# Quectel-2560-v2_3.net
KiCad netlist of a schematic drawn in EAGLE
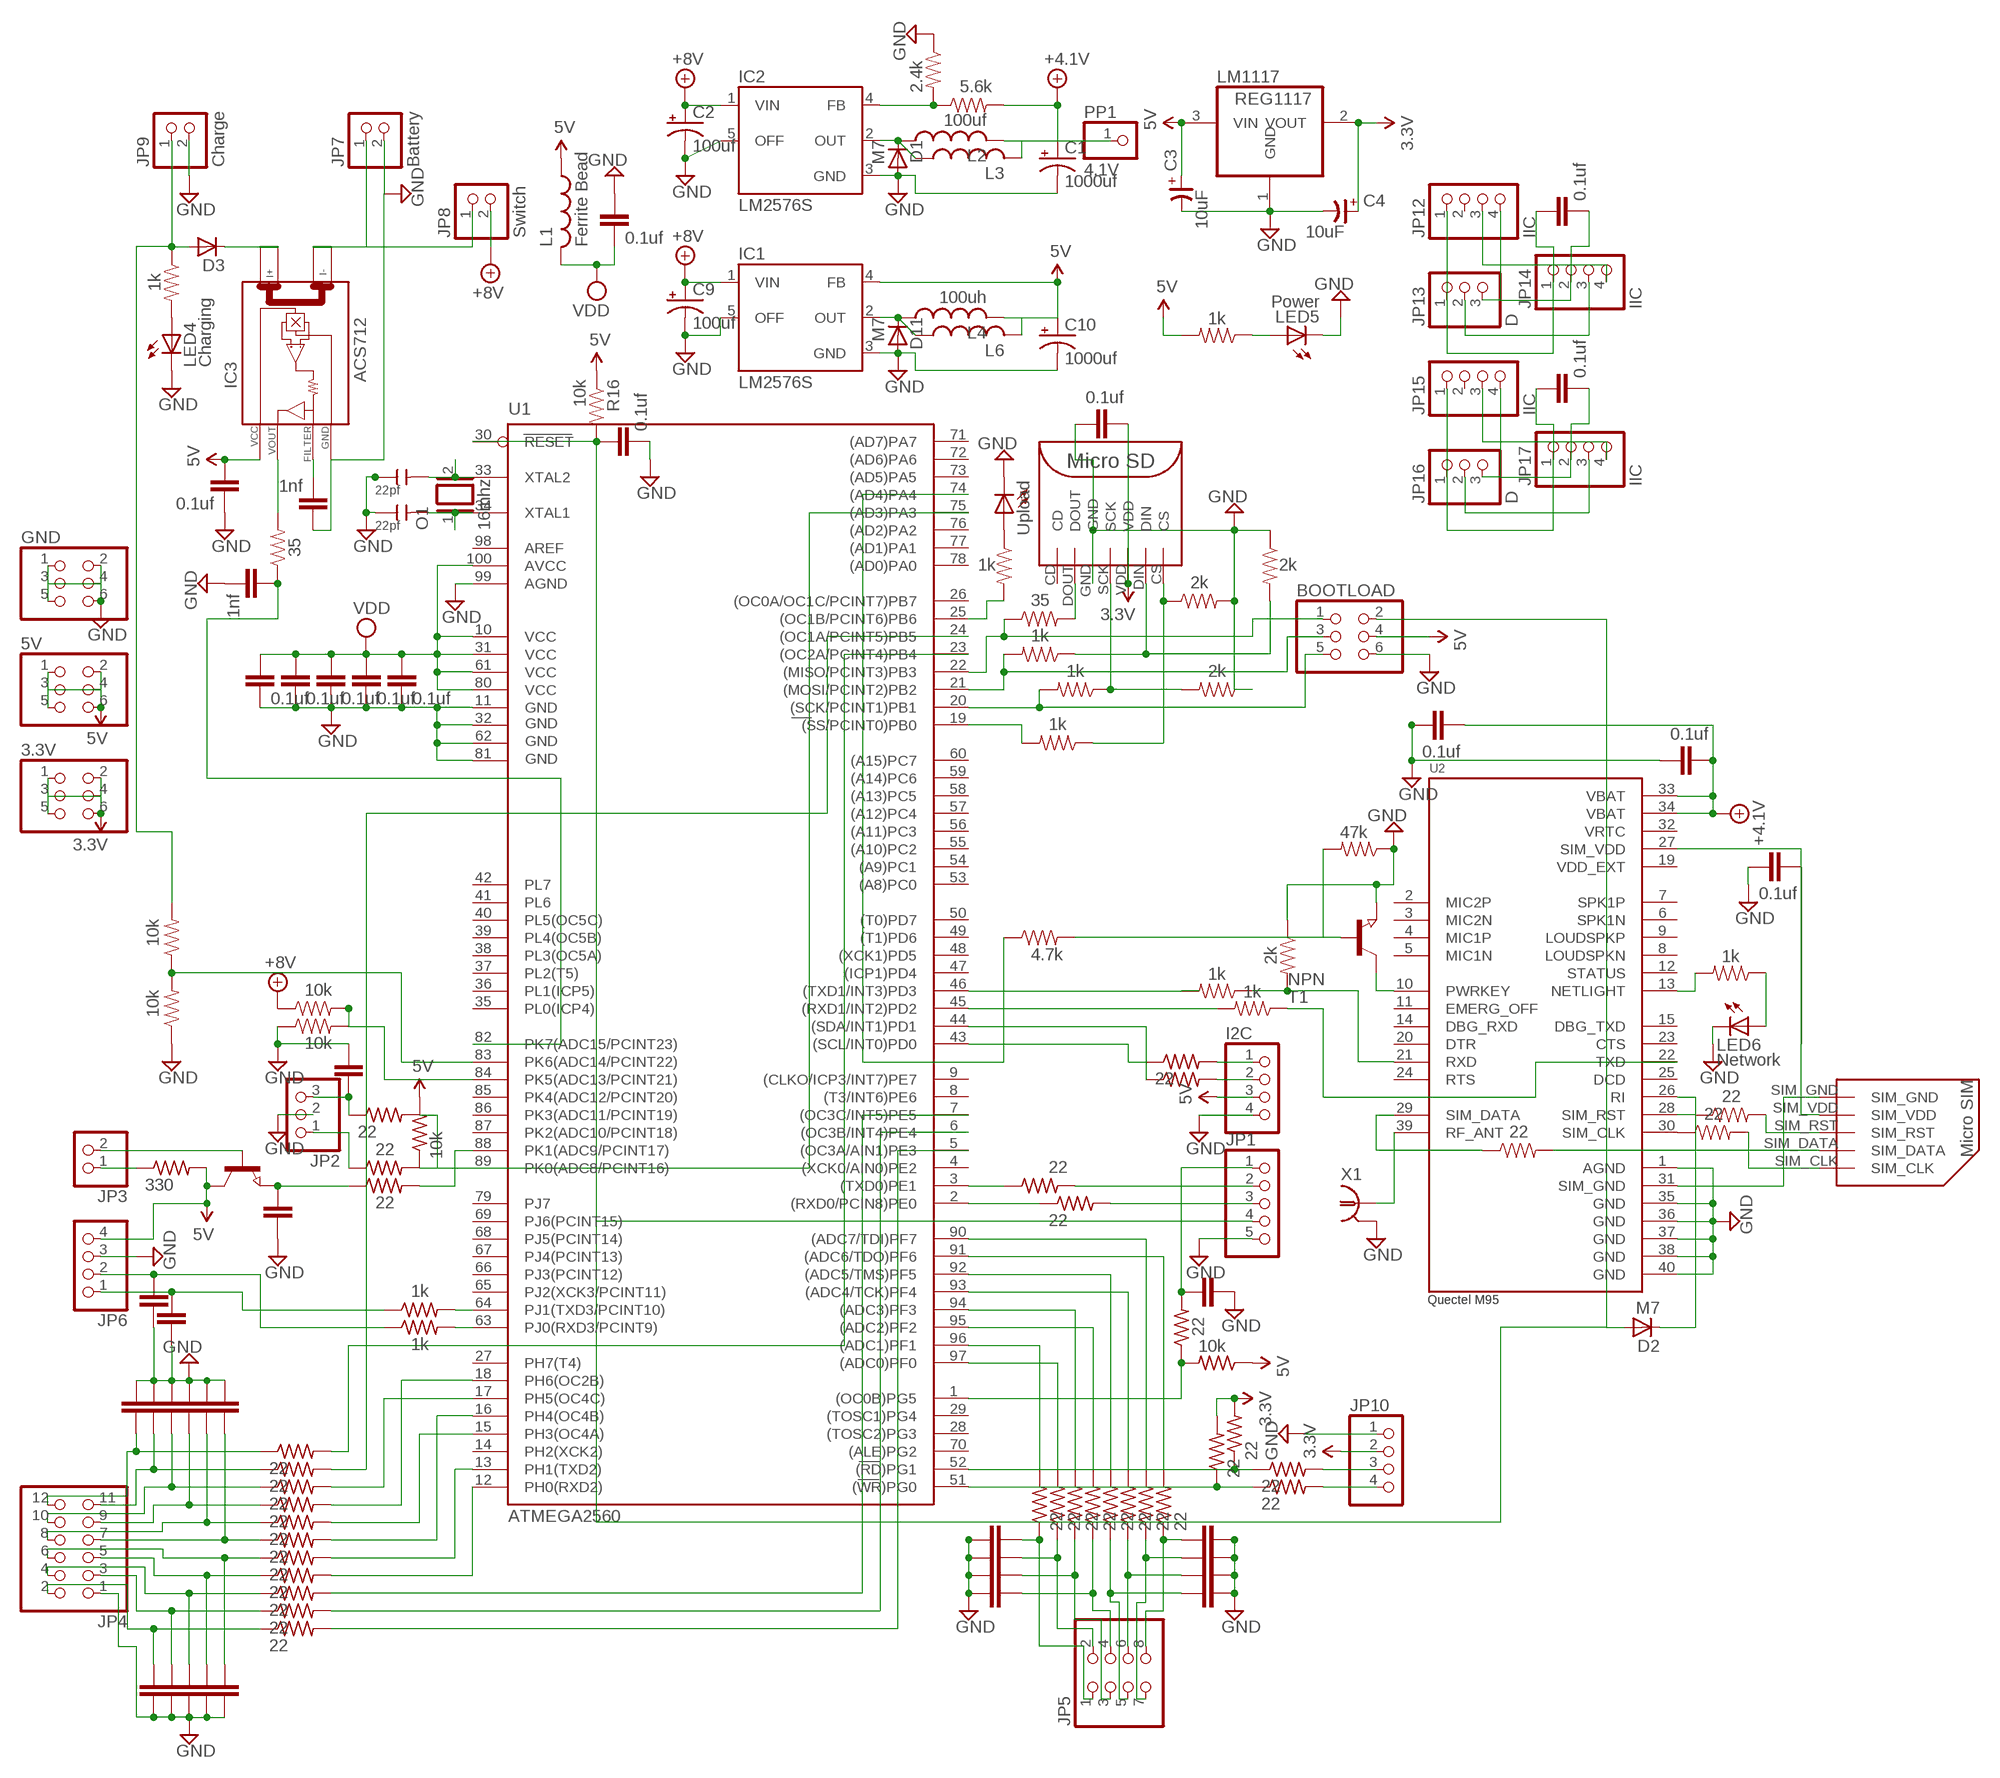
[diagram p0: schematic, sheet 1]

(export (version "E")
  (design (tool "Eeschema 10.0.6"))
  (components
    (comp (ref "3.3V")
      (value "PINHD-2X3")
      (footprint "eagle-import:2X03")
      (libsource (lib "eagle-import") (part "PINHD-2X3"))
    )
    (comp (ref "5V")
      (value "PINHD-2X3")
      (footprint "eagle-import:2X03")
      (libsource (lib "eagle-import") (part "PINHD-2X3"))
    )
    (comp (ref "BOOTLOAD")
      (value "PINHD-2X3")
      (footprint "eagle-import:2X03")
      (libsource (lib "eagle-import") (part "PINHD-2X3"))
    )
    (comp (ref "C1")
      (value "1000uf")
      (footprint "eagle-import:153CLV-1012")
      (libsource (lib "eagle-import") (part "CPOL-US153CLV-1012"))
    )
    (comp (ref "C2")
      (value "100uf")
      (footprint "eagle-import:CT7343")
      (libsource (lib "eagle-import") (part "CPOL-USCT7343"))
    )
    (comp (ref "C3")
      (value "10uF")
      (footprint "eagle-import:3528_T")
      (libsource (lib "eagle-import") (part "CP-3528"))
    )
    (comp (ref "C4")
      (value "10uF")
      (footprint "eagle-import:3528_T")
      (libsource (lib "eagle-import") (part "CP-3528"))
    )
    (comp (ref "C7")
      (value "22pf")
      (footprint "eagle-import:C0805")
      (fields (field (name "MPN") "CC0805JRNPO9BN220"))
      (libsource (lib "eagle-import") (part "CERAMIC-22PF-50V-5%-NPO(0805)"))
    )
    (comp (ref "C8")
      (value "22pf")
      (footprint "eagle-import:C0805")
      (fields (field (name "MPN") "CC0805JRNPO9BN220"))
      (libsource (lib "eagle-import") (part "CERAMIC-22PF-50V-5%-NPO(0805)"))
    )
    (comp (ref "C9")
      (value "100uf")
      (footprint "eagle-import:CT7343")
      (libsource (lib "eagle-import") (part "CPOL-USCT7343"))
    )
    (comp (ref "C10")
      (value "1000uf")
      (footprint "eagle-import:153CLV-1012")
      (libsource (lib "eagle-import") (part "CPOL-US153CLV-1012"))
    )
    (comp (ref "D1")
      (value "M7")
      (footprint "eagle-import:SOD106A")
      (fields (field (name "MPN") "BYS10/45"))
      (libsource (lib "eagle-import") (part "BYS10"))
    )
    (comp (ref "D2")
      (value "M7")
      (footprint "eagle-import:SOD106A")
      (fields (field (name "MPN") "BYS10/45"))
      (libsource (lib "eagle-import") (part "BYS10"))
    )
    (comp (ref "D3")
      (value "BYS10")
      (footprint "eagle-import:SOD106A")
      (fields (field (name "MPN") "BYS10/45"))
      (libsource (lib "eagle-import") (part "BYS10"))
    )
    (comp (ref "D11")
      (value "M7")
      (footprint "eagle-import:SOD106A")
      (fields (field (name "MPN") "BYS10/45"))
      (libsource (lib "eagle-import") (part "BYS10"))
    )
    (comp (ref "DC1")
      (value "0.1uf")
      (footprint "eagle-import:C0805")
      (libsource (lib "eagle-import") (part "C-EUC0805"))
    )
    (comp (ref "DC2")
      (value "0.1uf")
      (footprint "eagle-import:C0805")
      (libsource (lib "eagle-import") (part "C-EUC0805"))
    )
    (comp (ref "DC3")
      (value "0.1uf")
      (footprint "eagle-import:C0805")
      (libsource (lib "eagle-import") (part "C-EUC0805"))
    )
    (comp (ref "DC4")
      (value "0.1uf")
      (footprint "eagle-import:C0805")
      (libsource (lib "eagle-import") (part "C-EUC0805"))
    )
    (comp (ref "DC5")
      (value "0.1uf")
      (footprint "eagle-import:C0805")
      (libsource (lib "eagle-import") (part "C-EUC0805"))
    )
    (comp (ref "DC6")
      (value "0.1uf")
      (footprint "eagle-import:C0805")
      (libsource (lib "eagle-import") (part "C-EUC0805"))
    )
    (comp (ref "DC7")
      (value "0.1uf")
      (footprint "eagle-import:C0805")
      (libsource (lib "eagle-import") (part "C-EUC0805"))
    )
    (comp (ref "DC8")
      (value "0.1uf")
      (footprint "eagle-import:C0805")
      (libsource (lib "eagle-import") (part "C-EUC0805"))
    )
    (comp (ref "DC9")
      (value "0.1uf")
      (footprint "eagle-import:C0805")
      (libsource (lib "eagle-import") (part "C-EUC0805"))
    )
    (comp (ref "DC10")
      (value "0.1uf")
      (footprint "eagle-import:C0805")
      (libsource (lib "eagle-import") (part "C-EUC0805"))
    )
    (comp (ref "DC11")
      (value "0.1uf")
      (footprint "eagle-import:C0805")
      (libsource (lib "eagle-import") (part "C-EUC0805"))
    )
    (comp (ref "DC12")
      (value "1nf")
      (footprint "eagle-import:C0805")
      (libsource (lib "eagle-import") (part "C-EUC0805"))
    )
    (comp (ref "DC13")
      (value "1nf")
      (footprint "eagle-import:C0805")
      (libsource (lib "eagle-import") (part "C-EUC0805"))
    )
    (comp (ref "DC14")
      (value "1nf")
      (footprint "eagle-import:C0805")
      (libsource (lib "eagle-import") (part "C-EUC0805"))
    )
    (comp (ref "DC15")
      (value "0.1uf")
      (footprint "eagle-import:C0805")
      (libsource (lib "eagle-import") (part "C-EUC0805"))
    )
    (comp (ref "DC16")
      (value "1nf")
      (footprint "eagle-import:C0805")
      (libsource (lib "eagle-import") (part "C-EUC0805"))
    )
    (comp (ref "DC17")
      (value "1nf")
      (footprint "eagle-import:C0805")
      (libsource (lib "eagle-import") (part "C-EUC0805"))
    )
    (comp (ref "DC18")
      (value "0.1uf")
      (footprint "eagle-import:C0805")
      (libsource (lib "eagle-import") (part "C-EUC0805"))
    )
    (comp (ref "DC19")
      (value "0.1uf")
      (footprint "eagle-import:C0805")
      (libsource (lib "eagle-import") (part "C-EUC0805"))
    )
    (comp (ref "DC20")
      (value "1nf")
      (footprint "eagle-import:C0805")
      (libsource (lib "eagle-import") (part "C-EUC0805"))
    )
    (comp (ref "DC21")
      (value "1nf")
      (footprint "eagle-import:C0805")
      (libsource (lib "eagle-import") (part "C-EUC0805"))
    )
    (comp (ref "DC22")
      (value "1nf")
      (footprint "eagle-import:C0805")
      (libsource (lib "eagle-import") (part "C-EUC0805"))
    )
    (comp (ref "DC23")
      (value "1nf")
      (footprint "eagle-import:C0805")
      (libsource (lib "eagle-import") (part "C-EUC0805"))
    )
    (comp (ref "DC24")
      (value "1nf")
      (footprint "eagle-import:C0805")
      (libsource (lib "eagle-import") (part "C-EUC0805"))
    )
    (comp (ref "DC25")
      (value "1nf")
      (footprint "eagle-import:C0805")
      (libsource (lib "eagle-import") (part "C-EUC0805"))
    )
    (comp (ref "DC26")
      (value "1nf")
      (footprint "eagle-import:C0805")
      (libsource (lib "eagle-import") (part "C-EUC0805"))
    )
    (comp (ref "DC27")
      (value "1nf")
      (footprint "eagle-import:C0805")
      (libsource (lib "eagle-import") (part "C-EUC0805"))
    )
    (comp (ref "DC28")
      (value "1nf")
      (footprint "eagle-import:C0805")
      (libsource (lib "eagle-import") (part "C-EUC0805"))
    )
    (comp (ref "DC29")
      (value "1nf")
      (footprint "eagle-import:C0805")
      (libsource (lib "eagle-import") (part "C-EUC0805"))
    )
    (comp (ref "DC30")
      (value "1nf")
      (footprint "eagle-import:C0805")
      (libsource (lib "eagle-import") (part "C-EUC0805"))
    )
    (comp (ref "DC31")
      (value "1nf")
      (footprint "eagle-import:C0805")
      (libsource (lib "eagle-import") (part "C-EUC0805"))
    )
    (comp (ref "DC32")
      (value "1nf")
      (footprint "eagle-import:C0805")
      (libsource (lib "eagle-import") (part "C-EUC0805"))
    )
    (comp (ref "DC33")
      (value "1nf")
      (footprint "eagle-import:C0805")
      (libsource (lib "eagle-import") (part "C-EUC0805"))
    )
    (comp (ref "DC34")
      (value "1nf")
      (footprint "eagle-import:C0805")
      (libsource (lib "eagle-import") (part "C-EUC0805"))
    )
    (comp (ref "DC35")
      (value "1nf")
      (footprint "eagle-import:C0805")
      (libsource (lib "eagle-import") (part "C-EUC0805"))
    )
    (comp (ref "DC36")
      (value "1nf")
      (footprint "eagle-import:C0805")
      (libsource (lib "eagle-import") (part "C-EUC0805"))
    )
    (comp (ref "DC37")
      (value "1nf")
      (footprint "eagle-import:C0805")
      (libsource (lib "eagle-import") (part "C-EUC0805"))
    )
    (comp (ref "DC38")
      (value "1nf")
      (footprint "eagle-import:C0805")
      (libsource (lib "eagle-import") (part "C-EUC0805"))
    )
    (comp (ref "DC39")
      (value "1nf")
      (footprint "eagle-import:C0805")
      (libsource (lib "eagle-import") (part "C-EUC0805"))
    )
    (comp (ref "DC40")
      (value "1nf")
      (footprint "eagle-import:C0805")
      (libsource (lib "eagle-import") (part "C-EUC0805"))
    )
    (comp (ref "GND")
      (value "PINHD-2X3")
      (footprint "eagle-import:2X03")
      (libsource (lib "eagle-import") (part "PINHD-2X3"))
    )
    (comp (ref "I2C")
      (value "PINHD-1X4")
      (footprint "eagle-import:1X04")
      (libsource (lib "eagle-import") (part "pinhead_325_PINHD-1X4"))
    )
    (comp (ref "IC1")
      (value "LM2576S")
      (footprint "eagle-import:TO263-5")
      (libsource (lib "eagle-import") (part "LM2576S"))
    )
    (comp (ref "IC2")
      (value "LM2576S")
      (footprint "eagle-import:TO263-5")
      (libsource (lib "eagle-import") (part "LM2576S"))
    )
    (comp (ref "IC3")
      (value "ACS712")
      (footprint "eagle-import:SO08")
      (libsource (lib "eagle-import") (part "ACS712"))
    )
    (comp (ref "JP1")
      (value "PINHD-1X5")
      (footprint "eagle-import:1X05")
      (libsource (lib "eagle-import") (part "PINHD-1X5"))
    )
    (comp (ref "JP2")
      (value "PINHD-1X3")
      (footprint "eagle-import:1X03")
      (libsource (lib "eagle-import") (part "pinhead_325_PINHD-1X3"))
    )
    (comp (ref "JP3")
      (value "PINHD-1X2")
      (footprint "eagle-import:1X02")
      (libsource (lib "eagle-import") (part "pinhead_325_PINHD-1X2"))
    )
    (comp (ref "JP4")
      (value "PINHD-2X6")
      (footprint "eagle-import:2X06")
      (libsource (lib "eagle-import") (part "PINHD-2X6"))
    )
    (comp (ref "JP5")
      (value "PINHD-2X4")
      (footprint "eagle-import:2X04")
      (libsource (lib "eagle-import") (part "PINHD-2X4"))
    )
    (comp (ref "JP6")
      (value "PINHD-1X4")
      (footprint "eagle-import:1X04")
      (libsource (lib "eagle-import") (part "pinhead_325_PINHD-1X4"))
    )
    (comp (ref "JP7")
      (value "Battery")
      (footprint "eagle-import:1X02")
      (libsource (lib "eagle-import") (part "PINHD-1X2"))
    )
    (comp (ref "JP8")
      (value "Switch")
      (footprint "eagle-import:1X02")
      (libsource (lib "eagle-import") (part "PINHD-1X2"))
    )
    (comp (ref "JP9")
      (value "Charge")
      (footprint "eagle-import:1X02")
      (libsource (lib "eagle-import") (part "PINHD-1X2"))
    )
    (comp (ref "JP10")
      (value "PINHD-1X4")
      (footprint "eagle-import:1X04")
      (libsource (lib "eagle-import") (part "pinhead_325_PINHD-1X4"))
    )
    (comp (ref "JP12")
      (value "IIC")
      (footprint "eagle-import:1X04")
      (libsource (lib "eagle-import") (part "PINHD-1X4"))
    )
    (comp (ref "JP13")
      (value "D")
      (footprint "eagle-import:1X03")
      (libsource (lib "eagle-import") (part "PINHD-1X3"))
    )
    (comp (ref "JP14")
      (value "IIC")
      (footprint "eagle-import:1X04")
      (libsource (lib "eagle-import") (part "PINHD-1X4"))
    )
    (comp (ref "JP15")
      (value "IIC")
      (footprint "eagle-import:1X04")
      (libsource (lib "eagle-import") (part "PINHD-1X4"))
    )
    (comp (ref "JP16")
      (value "D")
      (footprint "eagle-import:1X03")
      (libsource (lib "eagle-import") (part "PINHD-1X3"))
    )
    (comp (ref "JP17")
      (value "IIC")
      (footprint "eagle-import:1X04")
      (libsource (lib "eagle-import") (part "PINHD-1X4"))
    )
    (comp (ref "L1")
      (value "Ferrite Bead")
      (footprint "eagle-import:L2012C")
      (libsource (lib "eagle-import") (part "L-USL2012C"))
    )
    (comp (ref "L2")
      (value "100uf")
      (footprint "eagle-import:PIS2816")
      (libsource (lib "eagle-import") (part "L-USPIS2816"))
    )
    (comp (ref "L3")
      (value "L-US6000-XXX-RC")
      (footprint "eagle-import:6000-XXXX-RC")
      (libsource (lib "eagle-import") (part "L-US6000-XXX-RC"))
    )
    (comp (ref "L4")
      (value "100uh")
      (footprint "eagle-import:PIS2816")
      (libsource (lib "eagle-import") (part "L-USPIS2816"))
    )
    (comp (ref "L6")
      (value "L-US6000-XXX-RC")
      (footprint "eagle-import:6000-XXXX-RC")
      (libsource (lib "eagle-import") (part "L-US6000-XXX-RC"))
    )
    (comp (ref "LED2")
      (value "Upload")
      (footprint "eagle-import:CHIP-LED0805")
      (libsource (lib "eagle-import") (part "LEDCHIP-LED0805"))
    )
    (comp (ref "LED4")
      (value "Charging")
      (footprint "eagle-import:CHIP-LED0805")
      (libsource (lib "eagle-import") (part "LEDCHIP-LED0805"))
    )
    (comp (ref "LED5")
      (value "Power")
      (footprint "eagle-import:CHIP-LED0805")
      (libsource (lib "eagle-import") (part "LEDCHIP-LED0805"))
    )
    (comp (ref "LED6")
      (value "Network")
      (footprint "eagle-import:CHIP-LED0805")
      (libsource (lib "eagle-import") (part "LEDCHIP-LED0805"))
    )
    (comp (ref "LM1117")
      (value "REG1117")
      (footprint "eagle-import:SOT223")
      (libsource (lib "eagle-import") (part "REG1117"))
    )
    (comp (ref "O1")
      (value "16mhz")
      (footprint "eagle-import:QS")
      (libsource (lib "eagle-import") (part "XTAL/S"))
    )
    (comp (ref "PP1")
      (value "4.1V")
      (footprint "eagle-import:1X01")
      (libsource (lib "eagle-import") (part "PINHD-1X1"))
    )
    (comp (ref "R1")
      (value "35")
      (footprint "eagle-import:0805")
      (libsource (lib "eagle-import") (part "RESISTOR0805-RES"))
    )
    (comp (ref "R2")
      (value "47k")
      (footprint "eagle-import:0805")
      (libsource (lib "eagle-import") (part "RESISTOR0805-RES"))
    )
    (comp (ref "R3")
      (value "4.7k")
      (footprint "eagle-import:0805")
      (libsource (lib "eagle-import") (part "RESISTOR0805-RES"))
    )
    (comp (ref "R4")
      (value "22")
      (footprint "eagle-import:R0805")
      (libsource (lib "eagle-import") (part "R-US_R0805"))
    )
    (comp (ref "R5")
      (value "22")
      (footprint "eagle-import:R0805")
      (libsource (lib "eagle-import") (part "R-US_R0805"))
    )
    (comp (ref "R6")
      (value "1k")
      (footprint "eagle-import:0805")
      (libsource (lib "eagle-import") (part "RESISTOR0805-RES"))
    )
    (comp (ref "R7")
      (value "1k")
      (footprint "eagle-import:0805")
      (libsource (lib "eagle-import") (part "RESISTOR0805-RES"))
    )
    (comp (ref "R8")
      (value "1k")
      (footprint "eagle-import:0805")
      (libsource (lib "eagle-import") (part "RESISTOR0805-RES"))
    )
    (comp (ref "R9")
      (value "2k")
      (footprint "eagle-import:0805")
      (libsource (lib "eagle-import") (part "RESISTOR0805-RES"))
    )
    (comp (ref "R10")
      (value "22")
      (footprint "eagle-import:0805")
      (libsource (lib "eagle-import") (part "RESISTOR0805-RES"))
    )
    (comp (ref "R11")
      (value "22")
      (footprint "eagle-import:0805")
      (libsource (lib "eagle-import") (part "RESISTOR0805-RES"))
    )
    (comp (ref "R12")
      (value "22")
      (footprint "eagle-import:R0805")
      (libsource (lib "eagle-import") (part "R-US_R0805"))
    )
    (comp (ref "R13")
      (value "22")
      (footprint "eagle-import:R0805")
      (libsource (lib "eagle-import") (part "R-US_R0805"))
    )
    (comp (ref "R14")
      (value "1k")
      (footprint "eagle-import:0805")
      (libsource (lib "eagle-import") (part "RESISTOR0805-RES"))
    )
    (comp (ref "R15")
      (value "1k")
      (footprint "eagle-import:0805")
      (libsource (lib "eagle-import") (part "RESISTOR0805-RES"))
    )
    (comp (ref "R16")
      (value "10k")
      (footprint "eagle-import:0805")
      (libsource (lib "eagle-import") (part "RESISTOR0805-RES"))
    )
    (comp (ref "R17")
      (value "1k")
      (footprint "eagle-import:0805")
      (libsource (lib "eagle-import") (part "RESISTOR0805-RES"))
    )
    (comp (ref "R18")
      (value "1k")
      (footprint "eagle-import:0805")
      (libsource (lib "eagle-import") (part "RESISTOR0805-RES"))
    )
    (comp (ref "R19")
      (value "22")
      (footprint "eagle-import:R0805")
      (libsource (lib "eagle-import") (part "R-US_R0805"))
    )
    (comp (ref "R20")
      (value "22")
      (footprint "eagle-import:R0805")
      (libsource (lib "eagle-import") (part "R-US_R0805"))
    )
    (comp (ref "R21")
      (value "22")
      (footprint "eagle-import:R0805")
      (libsource (lib "eagle-import") (part "R-US_R0805"))
    )
    (comp (ref "R22")
      (value "22")
      (footprint "eagle-import:R0805")
      (libsource (lib "eagle-import") (part "R-US_R0805"))
    )
    (comp (ref "R23")
      (value "2k")
      (footprint "eagle-import:0805")
      (libsource (lib "eagle-import") (part "RESISTOR0805-RES"))
    )
    (comp (ref "R24")
      (value "2k")
      (footprint "eagle-import:0805")
      (libsource (lib "eagle-import") (part "RESISTOR0805-RES"))
    )
    (comp (ref "R25")
      (value "1k")
      (footprint "eagle-import:0805")
      (libsource (lib "eagle-import") (part "RESISTOR0805-RES"))
    )
    (comp (ref "R26")
      (value "1k")
      (footprint "eagle-import:0805")
      (libsource (lib "eagle-import") (part "RESISTOR0805-RES"))
    )
    (comp (ref "R27")
      (value "22")
      (footprint "eagle-import:R0805")
      (libsource (lib "eagle-import") (part "R-US_R0805"))
    )
    (comp (ref "R28")
      (value "22")
      (footprint "eagle-import:R0805")
      (libsource (lib "eagle-import") (part "R-US_R0805"))
    )
    (comp (ref "R29")
      (value "2k")
      (footprint "eagle-import:0805")
      (libsource (lib "eagle-import") (part "RESISTOR0805-RES"))
    )
    (comp (ref "R30")
      (value "22")
      (footprint "eagle-import:R0805")
      (libsource (lib "eagle-import") (part "R-US_R0805"))
    )
    (comp (ref "R31")
      (value "22")
      (footprint "eagle-import:R0805")
      (libsource (lib "eagle-import") (part "R-US_R0805"))
    )
    (comp (ref "R32")
      (value "22")
      (footprint "eagle-import:R0805")
      (libsource (lib "eagle-import") (part "R-US_R0805"))
    )
    (comp (ref "R33")
      (value "22")
      (footprint "eagle-import:R0805")
      (libsource (lib "eagle-import") (part "R-US_R0805"))
    )
    (comp (ref "R34")
      (value "22")
      (footprint "eagle-import:R0805")
      (libsource (lib "eagle-import") (part "R-US_R0805"))
    )
    (comp (ref "R35")
      (value "35")
      (footprint "eagle-import:0805")
      (libsource (lib "eagle-import") (part "RESISTOR0805-RES"))
    )
    (comp (ref "R36")
      (value "22")
      (footprint "eagle-import:R0805")
      (libsource (lib "eagle-import") (part "R-US_R0805"))
    )
    (comp (ref "R37")
      (value "22")
      (footprint "eagle-import:R0805")
      (libsource (lib "eagle-import") (part "R-US_R0805"))
    )
    (comp (ref "R38")
      (value "22")
      (footprint "eagle-import:R0805")
      (libsource (lib "eagle-import") (part "R-US_R0805"))
    )
    (comp (ref "R39")
      (value "22")
      (footprint "eagle-import:R0805")
      (libsource (lib "eagle-import") (part "R-US_R0805"))
    )
    (comp (ref "R40")
      (value "22")
      (footprint "eagle-import:R0805")
      (libsource (lib "eagle-import") (part "R-US_R0805"))
    )
    (comp (ref "R41")
      (value "22")
      (footprint "eagle-import:R0805")
      (libsource (lib "eagle-import") (part "R-US_R0805"))
    )
    (comp (ref "R42")
      (value "22")
      (footprint "eagle-import:R0805")
      (libsource (lib "eagle-import") (part "R-US_R0805"))
    )
    (comp (ref "R43")
      (value "10k")
      (footprint "eagle-import:0805")
      (libsource (lib "eagle-import") (part "RESISTOR0805-RES"))
    )
    (comp (ref "R44")
      (value "10k")
      (footprint "eagle-import:0805")
      (libsource (lib "eagle-import") (part "RESISTOR0805-RES"))
    )
    (comp (ref "R45")
      (value "2.4k")
      (footprint "eagle-import:0805")
      (libsource (lib "eagle-import") (part "RESISTOR0805-RES"))
    )
    (comp (ref "R46")
      (value "5.6k")
      (footprint "eagle-import:0805")
      (libsource (lib "eagle-import") (part "RESISTOR0805-RES"))
    )
    (comp (ref "R47")
      (value "22")
      (footprint "eagle-import:0805")
      (libsource (lib "eagle-import") (part "RESISTOR0805-RES"))
    )
    (comp (ref "R48")
      (value "22")
      (footprint "eagle-import:R0805")
      (libsource (lib "eagle-import") (part "R-US_R0805"))
    )
    (comp (ref "R49")
      (value "22")
      (footprint "eagle-import:R0805")
      (libsource (lib "eagle-import") (part "R-US_R0805"))
    )
    (comp (ref "R50")
      (value "10k")
      (footprint "eagle-import:R0805")
      (libsource (lib "eagle-import") (part "R-US_R0805"))
    )
    (comp (ref "R51")
      (value "22")
      (footprint "eagle-import:R0805")
      (libsource (lib "eagle-import") (part "R-US_R0805"))
    )
    (comp (ref "R52")
      (value "330")
      (footprint "eagle-import:R0805")
      (libsource (lib "eagle-import") (part "R-US_R0805"))
    )
    (comp (ref "R53")
      (value "22")
      (footprint "eagle-import:R0805")
      (libsource (lib "eagle-import") (part "R-US_R0805"))
    )
    (comp (ref "R54")
      (value "22")
      (footprint "eagle-import:R0805")
      (libsource (lib "eagle-import") (part "R-US_R0805"))
    )
    (comp (ref "R55")
      (value "10k")
      (footprint "eagle-import:R0805")
      (libsource (lib "eagle-import") (part "R-US_R0805"))
    )
    (comp (ref "R56")
      (value "10k")
      (footprint "eagle-import:0805")
      (libsource (lib "eagle-import") (part "RESISTOR0805-RES"))
    )
    (comp (ref "R57")
      (value "10k")
      (footprint "eagle-import:0805")
      (libsource (lib "eagle-import") (part "RESISTOR0805-RES"))
    )
    (comp (ref "R58")
      (value "1k")
      (footprint "eagle-import:R0805")
      (libsource (lib "eagle-import") (part "R-US_R0805"))
    )
    (comp (ref "R59")
      (value "1k")
      (footprint "eagle-import:R0805")
      (libsource (lib "eagle-import") (part "R-US_R0805"))
    )
    (comp (ref "R60")
      (value "22")
      (footprint "eagle-import:R0805")
      (libsource (lib "eagle-import") (part "R-US_R0805"))
    )
    (comp (ref "R61")
      (value "22")
      (footprint "eagle-import:R0805")
      (libsource (lib "eagle-import") (part "R-US_R0805"))
    )
    (comp (ref "R62")
      (value "22")
      (footprint "eagle-import:R0805")
      (libsource (lib "eagle-import") (part "R-US_R0805"))
    )
    (comp (ref "R63")
      (value "22")
      (footprint "eagle-import:R0805")
      (libsource (lib "eagle-import") (part "R-US_R0805"))
    )
    (comp (ref "T1")
      (value "NPN")
      (footprint "eagle-import:SOT23")
      (libsource (lib "eagle-import") (part "NPN-TRANSISTOR_SOT23"))
    )
    (comp (ref "T2")
      (value "NPN")
      (footprint "eagle-import:SOT23")
      (libsource (lib "eagle-import") (part "NPN-TRANSISTOR_SOT23"))
    )
    (comp (ref "U$1")
      (value "MICROSD")
      (footprint "eagle-import:MICROSD")
      (libsource (lib "eagle-import") (part "MICROSD"))
    )
    (comp (ref "U$2")
      (value "MICROSIM")
      (footprint "eagle-import:MICROSIM")
      (libsource (lib "eagle-import") (part "MICROSIM"))
    )
    (comp (ref "U1")
      (value "ATMEGA2560")
      (footprint "eagle-import:TQFP100")
      (libsource (lib "eagle-import") (part "ATMEGA2560AU"))
    )
    (comp (ref "U2")
      (value "Quectel M95")
      (footprint "eagle-import:XCVR_M95")
      (libsource (lib "eagle-import") (part "M95"))
    )
    (comp (ref "X1")
      (value "LTI-SASF54GT")
      (footprint "eagle-import:LTI-SASF54GT")
      (libsource (lib "eagle-import") (part "LTI-SASF54GT"))
    )
  )
  (nets
    (net (code "1") (name "+4.1V") (class "Default")
      (node (ref "C1") (pin "+") (pinfunction "+_+") (pintype "passive"))
      (node (ref "DC6") (pin "2") (pinfunction "2_2") (pintype "passive"))
      (node (ref "DC7") (pin "2") (pinfunction "2_2") (pintype "passive"))
      (node (ref "L2") (pin "2") (pinfunction "2_2") (pintype "passive"))
      (node (ref "L3") (pin "2") (pinfunction "2_2") (pintype "passive"))
      (node (ref "PP1") (pin "1") (pinfunction "1_1") (pintype "passive"))
      (node (ref "R46") (pin "2") (pinfunction "2_2") (pintype "passive"))
      (node (ref "U2") (pin "33") (pinfunction "VBAT_33") (pintype "power_in"))
      (node (ref "U2") (pin "34") (pinfunction "VBAT_34") (pintype "power_in"))
    )
    (net (code "2") (name "+8V") (class "Default")
      (node (ref "C2") (pin "+") (pinfunction "+_+") (pintype "passive"))
      (node (ref "C9") (pin "+") (pinfunction "+_+") (pintype "passive"))
      (node (ref "IC1") (pin "1") (pinfunction "VIN_1") (pintype "power_in"))
      (node (ref "IC2") (pin "1") (pinfunction "VIN_1") (pintype "power_in"))
      (node (ref "JP8") (pin "2") (pinfunction "2_2") (pintype "passive"))
      (node (ref "R43") (pin "1") (pinfunction "1_1") (pintype "passive"))
    )
    (net (code "3") (name "/VDD_EXT") (class "Default")
      (node (ref "U2") (pin "19") (pinfunction "VDD_EXT_19") (pintype "power_in"))
    )
    (net (code "4") (name "/VRTC") (class "Default")
      (node (ref "U2") (pin "32") (pinfunction "VRTC_32") (pintype "power_in"))
    )
    (net (code "5") (name "3.3V") (class "Default")
      (node (ref "3.3V") (pin "1") (pinfunction "1_1") (pintype "passive"))
      (node (ref "3.3V") (pin "2") (pinfunction "2_2") (pintype "passive"))
      (node (ref "3.3V") (pin "3") (pinfunction "3_3") (pintype "passive"))
      (node (ref "3.3V") (pin "4") (pinfunction "4_4") (pintype "passive"))
      (node (ref "3.3V") (pin "5") (pinfunction "5_5") (pintype "passive"))
      (node (ref "3.3V") (pin "6") (pinfunction "6_6") (pintype "passive"))
      (node (ref "C4") (pin "+") (pinfunction "+_+") (pintype "passive"))
      (node (ref "DC10") (pin "2") (pinfunction "2_2") (pintype "passive"))
      (node (ref "JP10") (pin "2") (pinfunction "2_2") (pintype "passive"))
      (node (ref "LM1117") (pin "2") (pinfunction "VOUT_2") (pintype "output"))
      (node (ref "R62") (pin "2") (pinfunction "2_2") (pintype "passive"))
      (node (ref "R63") (pin "2") (pinfunction "2_2") (pintype "passive"))
      (node (ref "U$1") (pin "VDD") (pinfunction "VDD_VDD") (pintype "power_in"))
    )
    (net (code "6") (name "5V") (class "Default")
      (node (ref "5V") (pin "1") (pinfunction "1_1") (pintype "passive"))
      (node (ref "5V") (pin "2") (pinfunction "2_2") (pintype "passive"))
      (node (ref "5V") (pin "3") (pinfunction "3_3") (pintype "passive"))
      (node (ref "5V") (pin "4") (pinfunction "4_4") (pintype "passive"))
      (node (ref "5V") (pin "5") (pinfunction "5_5") (pintype "passive"))
      (node (ref "5V") (pin "6") (pinfunction "6_6") (pintype "passive"))
      (node (ref "BOOTLOAD") (pin "4") (pinfunction "4_4") (pintype "passive"))
      (node (ref "C10") (pin "+") (pinfunction "+_+") (pintype "passive"))
      (node (ref "C3") (pin "+") (pinfunction "+_+") (pintype "passive"))
      (node (ref "DC19") (pin "2") (pinfunction "2_2") (pintype "passive"))
      (node (ref "I2C") (pin "3") (pinfunction "3_3") (pintype "passive"))
      (node (ref "IC1") (pin "4") (pinfunction "FB_4") (pintype "input"))
      (node (ref "IC3") (pin "8") (pinfunction "VCC_8") (pintype "power_in"))
      (node (ref "JP6") (pin "4") (pinfunction "4_4") (pintype "passive"))
      (node (ref "L1") (pin "1") (pinfunction "1_1") (pintype "passive"))
      (node (ref "L4") (pin "2") (pinfunction "2_2") (pintype "passive"))
      (node (ref "L6") (pin "2") (pinfunction "2_2") (pintype "passive"))
      (node (ref "LM1117") (pin "3") (pinfunction "VIN_3") (pintype "input"))
      (node (ref "R16") (pin "1") (pinfunction "1_1") (pintype "passive"))
      (node (ref "R18") (pin "2") (pinfunction "2_2") (pintype "passive"))
      (node (ref "R50") (pin "1") (pinfunction "1_1") (pintype "passive"))
      (node (ref "R52") (pin "2") (pinfunction "2_2") (pintype "passive"))
      (node (ref "R55") (pin "2") (pinfunction "2_2") (pintype "passive"))
      (node (ref "T2") (pin "3") (pinfunction "C_3") (pintype "passive"))
    )
    (net (code "7") (name "GND") (class "Default")
      (node (ref "BOOTLOAD") (pin "6") (pinfunction "6_6") (pintype "passive"))
      (node (ref "C1") (pin "-") (pinfunction "-_-") (pintype "passive"))
      (node (ref "C10") (pin "-") (pinfunction "-_-") (pintype "passive"))
      (node (ref "C2") (pin "-") (pinfunction "-_-") (pintype "passive"))
      (node (ref "C3") (pin "-") (pinfunction "-_-") (pintype "passive"))
      (node (ref "C4") (pin "-") (pinfunction "-_-") (pintype "passive"))
      (node (ref "C7") (pin "1") (pinfunction "1_1") (pintype "passive"))
      (node (ref "C8") (pin "1") (pinfunction "1_1") (pintype "passive"))
      (node (ref "C9") (pin "-") (pinfunction "-_-") (pintype "passive"))
      (node (ref "D1") (pin "A") (pinfunction "A_A") (pintype "passive"))
      (node (ref "D11") (pin "A") (pinfunction "A_A") (pintype "passive"))
      (node (ref "DC1") (pin "2") (pinfunction "2_2") (pintype "passive"))
      (node (ref "DC10") (pin "1") (pinfunction "1_1") (pintype "passive"))
      (node (ref "DC11") (pin "2") (pinfunction "2_2") (pintype "passive"))
      (node (ref "DC12") (pin "1") (pinfunction "1_1") (pintype "passive"))
      (node (ref "DC13") (pin "1") (pinfunction "1_1") (pintype "passive"))
      (node (ref "DC14") (pin "1") (pinfunction "1_1") (pintype "passive"))
      (node (ref "DC15") (pin "1") (pinfunction "1_1") (pintype "passive"))
      (node (ref "DC16") (pin "1") (pinfunction "1_1") (pintype "passive"))
      (node (ref "DC17") (pin "1") (pinfunction "1_1") (pintype "passive"))
      (node (ref "DC18") (pin "1") (pinfunction "1_1") (pintype "passive"))
      (node (ref "DC19") (pin "1") (pinfunction "1_1") (pintype "passive"))
      (node (ref "DC2") (pin "2") (pinfunction "2_2") (pintype "passive"))
      (node (ref "DC20") (pin "1") (pinfunction "1_1") (pintype "passive"))
      (node (ref "DC21") (pin "2") (pinfunction "2_2") (pintype "passive"))
      (node (ref "DC22") (pin "1") (pinfunction "1_1") (pintype "passive"))
      (node (ref "DC23") (pin "2") (pinfunction "2_2") (pintype "passive"))
      (node (ref "DC24") (pin "2") (pinfunction "2_2") (pintype "passive"))
      (node (ref "DC25") (pin "2") (pinfunction "2_2") (pintype "passive"))
      (node (ref "DC26") (pin "2") (pinfunction "2_2") (pintype "passive"))
      (node (ref "DC27") (pin "2") (pinfunction "2_2") (pintype "passive"))
      (node (ref "DC28") (pin "2") (pinfunction "2_2") (pintype "passive"))
      (node (ref "DC29") (pin "2") (pinfunction "2_2") (pintype "passive"))
      (node (ref "DC3") (pin "2") (pinfunction "2_2") (pintype "passive"))
      (node (ref "DC30") (pin "2") (pinfunction "2_2") (pintype "passive"))
      (node (ref "DC31") (pin "2") (pinfunction "2_2") (pintype "passive"))
      (node (ref "DC32") (pin "2") (pinfunction "2_2") (pintype "passive"))
      (node (ref "DC33") (pin "1") (pinfunction "1_1") (pintype "passive"))
      (node (ref "DC34") (pin "1") (pinfunction "1_1") (pintype "passive"))
      (node (ref "DC35") (pin "1") (pinfunction "1_1") (pintype "passive"))
      (node (ref "DC36") (pin "1") (pinfunction "1_1") (pintype "passive"))
      (node (ref "DC37") (pin "2") (pinfunction "2_2") (pintype "passive"))
      (node (ref "DC38") (pin "2") (pinfunction "2_2") (pintype "passive"))
      (node (ref "DC39") (pin "1") (pinfunction "1_1") (pintype "passive"))
      (node (ref "DC4") (pin "2") (pinfunction "2_2") (pintype "passive"))
      (node (ref "DC40") (pin "2") (pinfunction "2_2") (pintype "passive"))
      (node (ref "DC5") (pin "2") (pinfunction "2_2") (pintype "passive"))
      (node (ref "DC6") (pin "1") (pinfunction "1_1") (pintype "passive"))
      (node (ref "DC7") (pin "1") (pinfunction "1_1") (pintype "passive"))
      (node (ref "GND") (pin "1") (pinfunction "1_1") (pintype "passive"))
      (node (ref "GND") (pin "2") (pinfunction "2_2") (pintype "passive"))
      (node (ref "GND") (pin "3") (pinfunction "3_3") (pintype "passive"))
      (node (ref "GND") (pin "4") (pinfunction "4_4") (pintype "passive"))
      (node (ref "GND") (pin "5") (pinfunction "5_5") (pintype "passive"))
      (node (ref "GND") (pin "6") (pinfunction "6_6") (pintype "passive"))
      (node (ref "I2C") (pin "4") (pinfunction "4_4") (pintype "passive"))
      (node (ref "IC1") (pin "3") (pinfunction "GND_3") (pintype "power_in"))
      (node (ref "IC1") (pin "5") (pinfunction "OFF_5") (pintype "input"))
      (node (ref "IC2") (pin "3") (pinfunction "GND_3") (pintype "power_in"))
      (node (ref "IC2") (pin "5") (pinfunction "OFF_5") (pintype "input"))
      (node (ref "IC3") (pin "5") (pinfunction "GND_5") (pintype "power_in"))
      (node (ref "JP1") (pin "5") (pinfunction "5_5") (pintype "passive"))
      (node (ref "JP10") (pin "1") (pinfunction "1_1") (pintype "passive"))
      (node (ref "JP2") (pin "2") (pinfunction "2_2") (pintype "passive"))
      (node (ref "JP4") (pin "1") (pinfunction "1_1") (pintype "passive"))
      (node (ref "JP6") (pin "3") (pinfunction "3_3") (pintype "passive"))
      (node (ref "JP7") (pin "2") (pinfunction "2_2") (pintype "passive"))
      (node (ref "JP9") (pin "2") (pinfunction "2_2") (pintype "passive"))
      (node (ref "LED2") (pin "C") (pinfunction "C_C") (pintype "passive"))
      (node (ref "LED4") (pin "C") (pinfunction "C_C") (pintype "passive"))
      (node (ref "LED5") (pin "C") (pinfunction "C_C") (pintype "passive"))
      (node (ref "LED6") (pin "C") (pinfunction "C_C") (pintype "passive"))
      (node (ref "LM1117") (pin "1") (pinfunction "GND_1") (pintype "power_in"))
      (node (ref "R2") (pin "1") (pinfunction "1_1") (pintype "passive"))
      (node (ref "R23") (pin "2") (pinfunction "2_2") (pintype "passive"))
      (node (ref "R24") (pin "1") (pinfunction "1_1") (pintype "passive"))
      (node (ref "R29") (pin "1") (pinfunction "1_1") (pintype "passive"))
      (node (ref "R44") (pin "1") (pinfunction "1_1") (pintype "passive"))
      (node (ref "R45") (pin "1") (pinfunction "1_1") (pintype "passive"))
      (node (ref "R57") (pin "1") (pinfunction "1_1") (pintype "passive"))
      (node (ref "R9") (pin "1") (pinfunction "1_1") (pintype "passive"))
      (node (ref "T1") (pin "2") (pinfunction "E_2") (pintype "passive"))
      (node (ref "U$1") (pin "GND") (pinfunction "GND_GND") (pintype "power_in"))
      (node (ref "U1") (pin "11") (pinfunction "GND_11") (pintype "power_in"))
      (node (ref "U1") (pin "32") (pinfunction "GND1_32") (pintype "power_in"))
      (node (ref "U1") (pin "62") (pinfunction "GND2_62") (pintype "power_in"))
      (node (ref "U1") (pin "81") (pinfunction "GND3_81") (pintype "power_in"))
      (node (ref "U1") (pin "99") (pinfunction "AGND_99") (pintype "power_in"))
      (node (ref "U2") (pin "1") (pinfunction "AGND_1") (pintype "power_in"))
      (node (ref "U2") (pin "35") (pinfunction "GND_35") (pintype "power_in"))
      (node (ref "U2") (pin "36") (pinfunction "GND_36") (pintype "power_in"))
      (node (ref "U2") (pin "37") (pinfunction "GND_37") (pintype "power_in"))
      (node (ref "U2") (pin "38") (pinfunction "GND_38") (pintype "input"))
      (node (ref "U2") (pin "40") (pinfunction "GND_40") (pintype "power_in"))
      (node (ref "X1") (pin "2") (pinfunction "2_2") (pintype "passive"))
      (node (ref "X1") (pin "3") (pinfunction "2_3") (pintype "passive"))
      (node (ref "X1") (pin "4") (pinfunction "2_4") (pintype "passive"))
      (node (ref "X1") (pin "5") (pinfunction "2_5") (pintype "passive"))
    )
    (net (code "8") (name "Net-(D3-PadA)") (class "Default")
      (node (ref "D3") (pin "A") (pinfunction "A_A") (pintype "passive"))
      (node (ref "JP9") (pin "1") (pinfunction "1_1") (pintype "passive"))
      (node (ref "R26") (pin "1") (pinfunction "1_1") (pintype "passive"))
      (node (ref "R56") (pin "2") (pinfunction "2_2") (pintype "passive"))
    )
    (net (code "9") (name "Net-(DC8-Pad1)") (class "Default")
      (node (ref "DC8") (pin "1") (pinfunction "1_1") (pintype "passive"))
      (node (ref "JP12") (pin "1") (pinfunction "1_1") (pintype "passive"))
      (node (ref "JP13") (pin "1") (pinfunction "1_1") (pintype "passive"))
      (node (ref "JP14") (pin "1") (pinfunction "1_1") (pintype "passive"))
    )
    (net (code "10") (name "Net-(DC8-Pad2)") (class "Default")
      (node (ref "DC8") (pin "2") (pinfunction "2_2") (pintype "passive"))
      (node (ref "JP12") (pin "4") (pinfunction "4_4") (pintype "passive"))
      (node (ref "JP13") (pin "3") (pinfunction "3_3") (pintype "passive"))
      (node (ref "JP14") (pin "2") (pinfunction "2_2") (pintype "passive"))
    )
    (net (code "11") (name "Net-(DC9-Pad1)") (class "Default")
      (node (ref "DC9") (pin "1") (pinfunction "1_1") (pintype "passive"))
      (node (ref "JP15") (pin "1") (pinfunction "1_1") (pintype "passive"))
      (node (ref "JP16") (pin "1") (pinfunction "1_1") (pintype "passive"))
      (node (ref "JP17") (pin "1") (pinfunction "1_1") (pintype "passive"))
    )
    (net (code "12") (name "Net-(DC9-Pad2)") (class "Default")
      (node (ref "DC9") (pin "2") (pinfunction "2_2") (pintype "passive"))
      (node (ref "JP15") (pin "4") (pinfunction "4_4") (pintype "passive"))
      (node (ref "JP16") (pin "3") (pinfunction "3_3") (pintype "passive"))
      (node (ref "JP17") (pin "2") (pinfunction "2_2") (pintype "passive"))
    )
    (net (code "13") (name "Net-(DC12-Pad2)") (class "Default")
      (node (ref "DC12") (pin "2") (pinfunction "2_2") (pintype "passive"))
      (node (ref "JP4") (pin "12") (pinfunction "12_12") (pintype "passive"))
      (node (ref "R4") (pin "1") (pinfunction "1_1") (pintype "passive"))
    )
    (net (code "14") (name "Net-(DC13-Pad2)") (class "Default")
      (node (ref "DC13") (pin "2") (pinfunction "2_2") (pintype "passive"))
      (node (ref "JP4") (pin "11") (pinfunction "11_11") (pintype "passive"))
      (node (ref "R5") (pin "1") (pinfunction "1_1") (pintype "passive"))
    )
    (net (code "15") (name "Net-(DC14-Pad2)") (class "Default")
      (node (ref "DC14") (pin "2") (pinfunction "2_2") (pintype "passive"))
      (node (ref "JP4") (pin "10") (pinfunction "10_10") (pintype "passive"))
      (node (ref "R12") (pin "1") (pinfunction "1_1") (pintype "passive"))
    )
    (net (code "16") (name "Net-(DC16-Pad2)") (class "Default")
      (node (ref "DC16") (pin "2") (pinfunction "2_2") (pintype "passive"))
      (node (ref "JP4") (pin "9") (pinfunction "9_9") (pintype "passive"))
      (node (ref "R13") (pin "1") (pinfunction "1_1") (pintype "passive"))
    )
    (net (code "17") (name "Net-(DC17-Pad2)") (class "Default")
      (node (ref "DC17") (pin "2") (pinfunction "2_2") (pintype "passive"))
      (node (ref "JP4") (pin "8") (pinfunction "8_8") (pintype "passive"))
      (node (ref "R19") (pin "1") (pinfunction "1_1") (pintype "passive"))
    )
    (net (code "18") (name "Net-(DC22-Pad2)") (class "Default")
      (node (ref "DC22") (pin "2") (pinfunction "2_2") (pintype "passive"))
      (node (ref "JP4") (pin "7") (pinfunction "7_7") (pintype "passive"))
      (node (ref "R20") (pin "1") (pinfunction "1_1") (pintype "passive"))
    )
    (net (code "19") (name "Net-(DC23-Pad1)") (class "Default")
      (node (ref "DC23") (pin "1") (pinfunction "1_1") (pintype "passive"))
      (node (ref "JP1") (pin "1") (pinfunction "1_1") (pintype "passive"))
      (node (ref "R33") (pin "2") (pinfunction "2_2") (pintype "passive"))
    )
    (net (code "20") (name "Net-(DC24-Pad1)") (class "Default")
      (node (ref "DC24") (pin "1") (pinfunction "1_1") (pintype "passive"))
      (node (ref "JP4") (pin "2") (pinfunction "2_2") (pintype "passive"))
      (node (ref "R32") (pin "1") (pinfunction "1_1") (pintype "passive"))
    )
    (net (code "21") (name "Net-(DC25-Pad1)") (class "Default")
      (node (ref "DC25") (pin "1") (pinfunction "1_1") (pintype "passive"))
      (node (ref "JP4") (pin "3") (pinfunction "3_3") (pintype "passive"))
      (node (ref "R31") (pin "1") (pinfunction "1_1") (pintype "passive"))
    )
    (net (code "22") (name "Net-(DC26-Pad1)") (class "Default")
      (node (ref "DC26") (pin "1") (pinfunction "1_1") (pintype "passive"))
      (node (ref "JP4") (pin "4") (pinfunction "4_4") (pintype "passive"))
      (node (ref "R30") (pin "1") (pinfunction "1_1") (pintype "passive"))
    )
    (net (code "23") (name "Net-(DC27-Pad1)") (class "Default")
      (node (ref "DC27") (pin "1") (pinfunction "1_1") (pintype "passive"))
      (node (ref "JP4") (pin "5") (pinfunction "5_5") (pintype "passive"))
      (node (ref "R22") (pin "1") (pinfunction "1_1") (pintype "passive"))
    )
    (net (code "24") (name "Net-(DC28-Pad1)") (class "Default")
      (node (ref "DC28") (pin "1") (pinfunction "1_1") (pintype "passive"))
      (node (ref "JP4") (pin "6") (pinfunction "6_6") (pintype "passive"))
      (node (ref "R21") (pin "1") (pinfunction "1_1") (pintype "passive"))
    )
    (net (code "25") (name "Net-(DC29-Pad1)") (class "Default")
      (node (ref "DC29") (pin "1") (pinfunction "1_1") (pintype "passive"))
      (node (ref "JP5") (pin "8") (pinfunction "8_8") (pintype "passive"))
      (node (ref "R40") (pin "1") (pinfunction "1_1") (pintype "passive"))
    )
    (net (code "26") (name "Net-(DC30-Pad1)") (class "Default")
      (node (ref "DC30") (pin "1") (pinfunction "1_1") (pintype "passive"))
      (node (ref "JP5") (pin "7") (pinfunction "7_7") (pintype "passive"))
      (node (ref "R39") (pin "1") (pinfunction "1_1") (pintype "passive"))
    )
    (net (code "27") (name "Net-(DC31-Pad1)") (class "Default")
      (node (ref "DC31") (pin "1") (pinfunction "1_1") (pintype "passive"))
      (node (ref "JP5") (pin "6") (pinfunction "6_6") (pintype "passive"))
      (node (ref "R37") (pin "1") (pinfunction "1_1") (pintype "passive"))
    )
    (net (code "28") (name "Net-(DC32-Pad1)") (class "Default")
      (node (ref "DC32") (pin "1") (pinfunction "1_1") (pintype "passive"))
      (node (ref "JP5") (pin "5") (pinfunction "5_5") (pintype "passive"))
      (node (ref "R38") (pin "1") (pinfunction "1_1") (pintype "passive"))
    )
    (net (code "29") (name "Net-(DC33-Pad2)") (class "Default")
      (node (ref "DC33") (pin "2") (pinfunction "2_2") (pintype "passive"))
      (node (ref "JP5") (pin "1") (pinfunction "1_1") (pintype "passive"))
      (node (ref "R27") (pin "1") (pinfunction "1_1") (pintype "passive"))
    )
    (net (code "30") (name "Net-(DC34-Pad2)") (class "Default")
      (node (ref "DC34") (pin "2") (pinfunction "2_2") (pintype "passive"))
      (node (ref "JP5") (pin "2") (pinfunction "2_2") (pintype "passive"))
      (node (ref "R28") (pin "1") (pinfunction "1_1") (pintype "passive"))
    )
    (net (code "31") (name "Net-(DC35-Pad2)") (class "Default")
      (node (ref "DC35") (pin "2") (pinfunction "2_2") (pintype "passive"))
      (node (ref "JP5") (pin "3") (pinfunction "3_3") (pintype "passive"))
      (node (ref "R34") (pin "1") (pinfunction "1_1") (pintype "passive"))
    )
    (net (code "32") (name "Net-(DC36-Pad2)") (class "Default")
      (node (ref "DC36") (pin "2") (pinfunction "2_2") (pintype "passive"))
      (node (ref "JP5") (pin "4") (pinfunction "4_4") (pintype "passive"))
      (node (ref "R36") (pin "1") (pinfunction "1_1") (pintype "passive"))
    )
    (net (code "33") (name "Net-(DC37-Pad1)") (class "Default")
      (node (ref "DC37") (pin "1") (pinfunction "1_1") (pintype "passive"))
      (node (ref "JP6") (pin "2") (pinfunction "2_2") (pintype "passive"))
      (node (ref "R59") (pin "1") (pinfunction "1_1") (pintype "passive"))
    )
    (net (code "34") (name "Net-(DC38-Pad1)") (class "Default")
      (node (ref "DC38") (pin "1") (pinfunction "1_1") (pintype "passive"))
      (node (ref "JP6") (pin "1") (pinfunction "1_1") (pintype "passive"))
      (node (ref "R58") (pin "1") (pinfunction "1_1") (pintype "passive"))
    )
    (net (code "35") (name "Net-(DC39-Pad2)") (class "Default")
      (node (ref "DC39") (pin "2") (pinfunction "2_2") (pintype "passive"))
      (node (ref "JP2") (pin "3") (pinfunction "3_3") (pintype "passive"))
      (node (ref "R51") (pin "1") (pinfunction "1_1") (pintype "passive"))
    )
    (net (code "36") (name "Net-(I2C-Pad1)") (class "Default")
      (node (ref "I2C") (pin "1") (pinfunction "1_1") (pintype "passive"))
      (node (ref "R49") (pin "2") (pinfunction "2_2") (pintype "passive"))
    )
    (net (code "37") (name "Net-(I2C-Pad2)") (class "Default")
      (node (ref "I2C") (pin "2") (pinfunction "2_2") (pintype "passive"))
      (node (ref "R48") (pin "2") (pinfunction "2_2") (pintype "passive"))
    )
    (net (code "38") (name "Net-(IC1-OUT)") (class "Default")
      (node (ref "D11") (pin "K") (pinfunction "K_K") (pintype "passive"))
      (node (ref "IC1") (pin "2") (pinfunction "OUT_2") (pintype "output"))
      (node (ref "L4") (pin "1") (pinfunction "1_1") (pintype "passive"))
      (node (ref "L6") (pin "1") (pinfunction "1_1") (pintype "passive"))
    )
    (net (code "39") (name "Net-(IC2-FB)") (class "Default")
      (node (ref "IC2") (pin "4") (pinfunction "FB_4") (pintype "input"))
      (node (ref "R45") (pin "2") (pinfunction "2_2") (pintype "passive"))
      (node (ref "R46") (pin "1") (pinfunction "1_1") (pintype "passive"))
    )
    (net (code "40") (name "Net-(IC2-OUT)") (class "Default")
      (node (ref "D1") (pin "K") (pinfunction "K_K") (pintype "passive"))
      (node (ref "IC2") (pin "2") (pinfunction "OUT_2") (pintype "output"))
      (node (ref "L2") (pin "1") (pinfunction "1_1") (pintype "passive"))
      (node (ref "L3") (pin "1") (pinfunction "1_1") (pintype "passive"))
    )
    (net (code "41") (name "Net-(IC3-FILTER)") (class "Default")
      (node (ref "DC20") (pin "2") (pinfunction "2_2") (pintype "passive"))
      (node (ref "IC3") (pin "6") (pinfunction "FILTER_6") (pintype "bidirectional"))
    )
    (net (code "42") (name "Net-(IC3-I+_0)") (class "Default")
      (node (ref "D3") (pin "K") (pinfunction "K_K") (pintype "passive"))
      (node (ref "IC3") (pin "1") (pinfunction "I+_0_1") (pintype "bidirectional"))
    )
    (net (code "43") (name "Net-(IC3-I-_1)") (class "Default")
      (node (ref "IC3") (pin "4") (pinfunction "I-_1_4") (pintype "bidirectional"))
      (node (ref "JP7") (pin "1") (pinfunction "1_1") (pintype "passive"))
      (node (ref "JP8") (pin "1") (pinfunction "1_1") (pintype "passive"))
    )
    (net (code "44") (name "Net-(IC3-VOUT)") (class "Default")
      (node (ref "IC3") (pin "7") (pinfunction "VOUT_7") (pintype "output"))
      (node (ref "R1") (pin "2") (pinfunction "2_2") (pintype "passive"))
    )
    (net (code "45") (name "Net-(JP1-Pad2)") (class "Default")
      (node (ref "JP1") (pin "2") (pinfunction "2_2") (pintype "passive"))
      (node (ref "R41") (pin "2") (pinfunction "2_2") (pintype "passive"))
    )
    (net (code "46") (name "Net-(JP1-Pad3)") (class "Default")
      (node (ref "JP1") (pin "3") (pinfunction "3_3") (pintype "passive"))
      (node (ref "R42") (pin "2") (pinfunction "2_2") (pintype "passive"))
    )
    (net (code "47") (name "Net-(JP2-Pad1)") (class "Default")
      (node (ref "JP2") (pin "1") (pinfunction "1_1") (pintype "passive"))
      (node (ref "R54") (pin "1") (pinfunction "1_1") (pintype "passive"))
    )
    (net (code "48") (name "Net-(JP3-Pad1)") (class "Default")
      (node (ref "JP3") (pin "1") (pinfunction "1_1") (pintype "passive"))
      (node (ref "R52") (pin "1") (pinfunction "1_1") (pintype "passive"))
    )
    (net (code "49") (name "Net-(JP10-Pad3)") (class "Default")
      (node (ref "JP10") (pin "3") (pinfunction "3_3") (pintype "passive"))
      (node (ref "R61") (pin "2") (pinfunction "2_2") (pintype "passive"))
    )
    (net (code "50") (name "Net-(JP10-Pad4)") (class "Default")
      (node (ref "JP10") (pin "4") (pinfunction "4_4") (pintype "passive"))
      (node (ref "R60") (pin "2") (pinfunction "2_2") (pintype "passive"))
    )
    (net (code "51") (name "Net-(JP12-Pad3)") (class "Default")
      (node (ref "JP12") (pin "3") (pinfunction "3_3") (pintype "passive"))
      (node (ref "JP14") (pin "4") (pinfunction "4_4") (pintype "passive"))
    )
    (net (code "52") (name "Net-(JP13-Pad2)") (class "Default")
      (node (ref "JP13") (pin "2") (pinfunction "2_2") (pintype "passive"))
      (node (ref "JP14") (pin "3") (pinfunction "3_3") (pintype "passive"))
    )
    (net (code "53") (name "Net-(JP15-Pad3)") (class "Default")
      (node (ref "JP15") (pin "3") (pinfunction "3_3") (pintype "passive"))
      (node (ref "JP17") (pin "4") (pinfunction "4_4") (pintype "passive"))
    )
    (net (code "54") (name "Net-(JP16-Pad2)") (class "Default")
      (node (ref "JP16") (pin "2") (pinfunction "2_2") (pintype "passive"))
      (node (ref "JP17") (pin "3") (pinfunction "3_3") (pintype "passive"))
    )
    (net (code "55") (name "Net-(LED2-PadA)") (class "Default")
      (node (ref "LED2") (pin "A") (pinfunction "A_A") (pintype "passive"))
      (node (ref "R25") (pin "1") (pinfunction "1_1") (pintype "passive"))
    )
    (net (code "56") (name "Net-(LED4-PadA)") (class "Default")
      (node (ref "LED4") (pin "A") (pinfunction "A_A") (pintype "passive"))
      (node (ref "R26") (pin "2") (pinfunction "2_2") (pintype "passive"))
    )
    (net (code "57") (name "Net-(LED5-PadA)") (class "Default")
      (node (ref "LED5") (pin "A") (pinfunction "A_A") (pintype "passive"))
      (node (ref "R18") (pin "1") (pinfunction "1_1") (pintype "passive"))
    )
    (net (code "58") (name "Net-(LED6-PadA)") (class "Default")
      (node (ref "LED6") (pin "A") (pinfunction "A_A") (pintype "passive"))
      (node (ref "R17") (pin "1") (pinfunction "1_1") (pintype "passive"))
    )
    (net (code "59") (name "Net-(R6-Pad1)") (class "Default")
      (node (ref "R6") (pin "1") (pinfunction "1_1") (pintype "passive"))
      (node (ref "R9") (pin "2") (pinfunction "2_2") (pintype "passive"))
      (node (ref "U$1") (pin "DIN") (pinfunction "DIN_DIN") (pintype "input"))
    )
    (net (code "60") (name "Net-(R10-Pad2)") (class "Default")
      (node (ref "R10") (pin "2") (pinfunction "2_2") (pintype "passive"))
      (node (ref "U$2") (pin "SIM_RST") (pinfunction "SIM_RST_SIM_RST") (pintype "bidirectional"))
    )
    (net (code "61") (name "Net-(R11-Pad2)") (class "Default")
      (node (ref "R11") (pin "2") (pinfunction "2_2") (pintype "passive"))
      (node (ref "U$2") (pin "SIM_CLK") (pinfunction "SIM_CLK_SIM_CLK") (pintype "bidirectional"))
    )
    (net (code "62") (name "Net-(R23-Pad1)") (class "Default")
      (node (ref "R23") (pin "1") (pinfunction "1_1") (pintype "passive"))
      (node (ref "R8") (pin "1") (pinfunction "1_1") (pintype "passive"))
      (node (ref "U$1") (pin "CS") (pinfunction "CS_CS") (pintype "bidirectional"))
    )
    (net (code "63") (name "Net-(R24-Pad2)") (class "Default")
      (node (ref "R24") (pin "2") (pinfunction "2_2") (pintype "passive"))
      (node (ref "R7") (pin "1") (pinfunction "1_1") (pintype "passive"))
      (node (ref "U$1") (pin "SCK") (pinfunction "SCK_SCK") (pintype "bidirectional"))
    )
    (net (code "64") (name "Net-(R35-Pad2)") (class "Default")
      (node (ref "R35") (pin "2") (pinfunction "2_2") (pintype "passive"))
      (node (ref "U$1") (pin "DOUT") (pinfunction "DOUT_DOUT") (pintype "output"))
    )
    (net (code "65") (name "Net-(R47-Pad2)") (class "Default")
      (node (ref "R47") (pin "2") (pinfunction "2_2") (pintype "passive"))
      (node (ref "U$2") (pin "SIM_DATA") (pinfunction "SIM_DATA_SIM_DATA") (pintype "bidirectional"))
    )
    (net (code "66") (name "Net-(T1-B)") (class "Default")
      (node (ref "R2") (pin "2") (pinfunction "2_2") (pintype "passive"))
      (node (ref "R3") (pin "2") (pinfunction "2_2") (pintype "passive"))
      (node (ref "T1") (pin "1") (pinfunction "B_1") (pintype "passive"))
    )
    (net (code "67") (name "Net-(T1-C)") (class "Default")
      (node (ref "T1") (pin "3") (pinfunction "C_3") (pintype "passive"))
      (node (ref "U2") (pin "10") (pinfunction "PWRKEY_10") (pintype "input"))
    )
    (net (code "68") (name "Net-(T2-B)") (class "Default")
      (node (ref "JP3") (pin "2") (pinfunction "2_2") (pintype "passive"))
      (node (ref "T2") (pin "1") (pinfunction "B_1") (pintype "passive"))
    )
    (net (code "69") (name "Net-(T2-E)") (class "Default")
      (node (ref "DC40") (pin "1") (pinfunction "1_1") (pintype "passive"))
      (node (ref "R53") (pin "1") (pinfunction "1_1") (pintype "passive"))
      (node (ref "T2") (pin "2") (pinfunction "E_2") (pintype "passive"))
    )
    (net (code "70") (name "Net-(U1-(AD3)PA3)") (class "Default")
      (node (ref "R54") (pin "2") (pinfunction "2_2") (pintype "passive"))
      (node (ref "R55") (pin "1") (pinfunction "1_1") (pintype "passive"))
      (node (ref "U1") (pin "75") (pinfunction "(AD3)PA3_75") (pintype "bidirectional"))
    )
    (net (code "71") (name "Net-(U1-(AD4)PA4)") (class "Default")
      (node (ref "R3") (pin "1") (pinfunction "1_1") (pintype "passive"))
      (node (ref "U1") (pin "74") (pinfunction "(AD4)PA4_74") (pintype "bidirectional"))
    )
    (net (code "72") (name "Net-(U1-(ADC0)PF0)") (class "Default")
      (node (ref "R28") (pin "2") (pinfunction "2_2") (pintype "passive"))
      (node (ref "U1") (pin "97") (pinfunction "(ADC0)PF0_97") (pintype "bidirectional"))
    )
    (net (code "73") (name "Net-(U1-(ADC1)PF1)") (class "Default")
      (node (ref "R27") (pin "2") (pinfunction "2_2") (pintype "passive"))
      (node (ref "U1") (pin "96") (pinfunction "(ADC1)PF1_96") (pintype "bidirectional"))
    )
    (net (code "74") (name "Net-(U1-(ADC2)PF2)") (class "Default")
      (node (ref "R36") (pin "2") (pinfunction "2_2") (pintype "passive"))
      (node (ref "U1") (pin "95") (pinfunction "(ADC2)PF2_95") (pintype "bidirectional"))
    )
    (net (code "75") (name "Net-(U1-(ADC3)PF3)") (class "Default")
      (node (ref "R34") (pin "2") (pinfunction "2_2") (pintype "passive"))
      (node (ref "U1") (pin "94") (pinfunction "(ADC3)PF3_94") (pintype "bidirectional"))
    )
    (net (code "76") (name "Net-(U1-(ADC4{slash}TCK)PF4)") (class "Default")
      (node (ref "R37") (pin "2") (pinfunction "2_2") (pintype "passive"))
      (node (ref "U1") (pin "93") (pinfunction "(ADC4/TCK)PF4_93") (pintype "bidirectional"))
    )
    (net (code "77") (name "Net-(U1-(ADC5{slash}TMS)PF5)") (class "Default")
      (node (ref "R38") (pin "2") (pinfunction "2_2") (pintype "passive"))
      (node (ref "U1") (pin "92") (pinfunction "(ADC5/TMS)PF5_92") (pintype "bidirectional"))
    )
    (net (code "78") (name "Net-(U1-(ADC6{slash}TDO)PF6)") (class "Default")
      (node (ref "R40") (pin "2") (pinfunction "2_2") (pintype "passive"))
      (node (ref "U1") (pin "91") (pinfunction "(ADC6/TDO)PF6_91") (pintype "bidirectional"))
    )
    (net (code "79") (name "Net-(U1-(ADC7{slash}TDI)PF7)") (class "Default")
      (node (ref "R39") (pin "2") (pinfunction "2_2") (pintype "passive"))
      (node (ref "U1") (pin "90") (pinfunction "(ADC7/TDI)PF7_90") (pintype "bidirectional"))
    )
    (net (code "80") (name "Net-(U1-(MISO{slash}PCINT3)PB3)") (class "Default")
      (node (ref "BOOTLOAD") (pin "1") (pinfunction "1_1") (pintype "passive"))
      (node (ref "R35") (pin "1") (pinfunction "1_1") (pintype "passive"))
      (node (ref "U1") (pin "22") (pinfunction "(MISO/PCINT3)PB3_22") (pintype "bidirectional"))
    )
    (net (code "81") (name "Net-(U1-(MOSI{slash}PCINT2)PB2)") (class "Default")
      (node (ref "BOOTLOAD") (pin "3") (pinfunction "3_3") (pintype "passive"))
      (node (ref "R6") (pin "2") (pinfunction "2_2") (pintype "passive"))
      (node (ref "U1") (pin "21") (pinfunction "(MOSI/PCINT2)PB2_21") (pintype "bidirectional"))
    )
    (net (code "82") (name "Net-(U1-(OC0B)PG5)") (class "Default")
      (node (ref "R33") (pin "1") (pinfunction "1_1") (pintype "passive"))
      (node (ref "R50") (pin "2") (pinfunction "2_2") (pintype "passive"))
      (node (ref "U1") (pin "1") (pinfunction "(OC0B)PG5_1") (pintype "bidirectional"))
    )
    (net (code "83") (name "Net-(U1-(OC1A{slash}PCINT5)PB5)") (class "Default")
      (node (ref "R5") (pin "2") (pinfunction "2_2") (pintype "passive"))
      (node (ref "U1") (pin "24") (pinfunction "(OC1A/PCINT5)PB5_24") (pintype "bidirectional"))
    )
    (net (code "84") (name "Net-(U1-(OC1B{slash}PCINT6)PB6)") (class "Default")
      (node (ref "R25") (pin "2") (pinfunction "2_2") (pintype "passive"))
      (node (ref "U1") (pin "25") (pinfunction "(OC1B/PCINT6)PB6_25") (pintype "bidirectional"))
    )
    (net (code "85") (name "Net-(U1-(OC2A{slash}PCINT4)PB4)") (class "Default")
      (node (ref "R4") (pin "2") (pinfunction "2_2") (pintype "passive"))
      (node (ref "U1") (pin "23") (pinfunction "(OC2A/PCINT4)PB4_23") (pintype "bidirectional"))
    )
    (net (code "86") (name "Net-(U1-(OC3A{slash}AIN1)PE3)") (class "Default")
      (node (ref "R32") (pin "2") (pinfunction "2_2") (pintype "passive"))
      (node (ref "U1") (pin "5") (pinfunction "(OC3A/AIN1)PE3_5") (pintype "bidirectional"))
    )
    (net (code "87") (name "Net-(U1-(OC3B{slash}INT4)PE4)") (class "Default")
      (node (ref "R31") (pin "2") (pinfunction "2_2") (pintype "passive"))
      (node (ref "U1") (pin "6") (pinfunction "(OC3B/INT4)PE4_6") (pintype "bidirectional"))
    )
    (net (code "88") (name "Net-(U1-(OC3C{slash}INT5)PE5)") (class "Default")
      (node (ref "R30") (pin "2") (pinfunction "2_2") (pintype "passive"))
      (node (ref "U1") (pin "7") (pinfunction "(OC3C/INT5)PE5_7") (pintype "bidirectional"))
    )
    (net (code "89") (name "Net-(U1-(RD)PG1)") (class "Default")
      (node (ref "R61") (pin "1") (pinfunction "1_1") (pintype "passive"))
      (node (ref "R63") (pin "1") (pinfunction "1_1") (pintype "passive"))
      (node (ref "U1") (pin "52") (pinfunction "(RD)PG1_52") (pintype "bidirectional"))
    )
    (net (code "90") (name "Net-(U1-(RXD0{slash}PCIN8)PE0)") (class "Default")
      (node (ref "R42") (pin "1") (pinfunction "1_1") (pintype "passive"))
      (node (ref "U1") (pin "2") (pinfunction "(RXD0/PCIN8)PE0_2") (pintype "bidirectional"))
    )
    (net (code "91") (name "Net-(U1-(RXD1{slash}INT2)PD2)") (class "Default")
      (node (ref "R15") (pin "2") (pinfunction "2_2") (pintype "passive"))
      (node (ref "U1") (pin "45") (pinfunction "(RXD1/INT2)PD2_45") (pintype "bidirectional"))
    )
    (net (code "92") (name "Net-(U1-(SCK{slash}PCINT1)PB1)") (class "Default")
      (node (ref "BOOTLOAD") (pin "5") (pinfunction "5_5") (pintype "passive"))
      (node (ref "R7") (pin "2") (pinfunction "2_2") (pintype "passive"))
      (node (ref "U1") (pin "20") (pinfunction "(SCK/PCINT1)PB1_20") (pintype "bidirectional"))
    )
    (net (code "93") (name "Net-(U1-(SCL{slash}INT0)PD0)") (class "Default")
      (node (ref "R49") (pin "1") (pinfunction "1_1") (pintype "passive"))
      (node (ref "U1") (pin "43") (pinfunction "(SCL/INT0)PD0_43") (pintype "bidirectional"))
    )
    (net (code "94") (name "Net-(U1-(SDA{slash}INT1)PD1)") (class "Default")
      (node (ref "R48") (pin "1") (pinfunction "1_1") (pintype "passive"))
      (node (ref "U1") (pin "44") (pinfunction "(SDA/INT1)PD1_44") (pintype "bidirectional"))
    )
    (net (code "95") (name "Net-(U1-(SS{slash}PCINT0)PB0)") (class "Default")
      (node (ref "R8") (pin "2") (pinfunction "2_2") (pintype "passive"))
      (node (ref "U1") (pin "19") (pinfunction "(SS/PCINT0)PB0_19") (pintype "bidirectional"))
    )
    (net (code "96") (name "Net-(U1-(TXD0)PE1)") (class "Default")
      (node (ref "R41") (pin "1") (pinfunction "1_1") (pintype "passive"))
      (node (ref "U1") (pin "3") (pinfunction "(TXD0)PE1_3") (pintype "bidirectional"))
    )
    (net (code "97") (name "Net-(U1-(TXD1{slash}INT3)PD3)") (class "Default")
      (node (ref "R14") (pin "2") (pinfunction "2_2") (pintype "passive"))
      (node (ref "U1") (pin "46") (pinfunction "(TXD1/INT3)PD3_46") (pintype "bidirectional"))
    )
    (net (code "98") (name "Net-(U1-(WR)PG0)") (class "Default")
      (node (ref "R60") (pin "1") (pinfunction "1_1") (pintype "passive"))
      (node (ref "R62") (pin "1") (pinfunction "1_1") (pintype "passive"))
      (node (ref "U1") (pin "51") (pinfunction "(WR)PG0_51") (pintype "bidirectional"))
    )
    (net (code "99") (name "Net-(U1-PH0(RXD2))") (class "Default")
      (node (ref "R22") (pin "2") (pinfunction "2_2") (pintype "passive"))
      (node (ref "U1") (pin "12") (pinfunction "PH0(RXD2)_12") (pintype "bidirectional"))
    )
    (net (code "100") (name "Net-(U1-PH1(TXD2))") (class "Default")
      (node (ref "R21") (pin "2") (pinfunction "2_2") (pintype "passive"))
      (node (ref "U1") (pin "13") (pinfunction "PH1(TXD2)_13") (pintype "bidirectional"))
    )
    (net (code "101") (name "Net-(U1-PH3(OC4A))") (class "Default")
      (node (ref "R19") (pin "2") (pinfunction "2_2") (pintype "passive"))
      (node (ref "U1") (pin "15") (pinfunction "PH3(OC4A)_15") (pintype "bidirectional"))
    )
    (net (code "102") (name "Net-(U1-PH4(OC4B))") (class "Default")
      (node (ref "R20") (pin "2") (pinfunction "2_2") (pintype "passive"))
      (node (ref "U1") (pin "16") (pinfunction "PH4(OC4B)_16") (pintype "bidirectional"))
    )
    (net (code "103") (name "Net-(U1-PH5(OC4C))") (class "Default")
      (node (ref "R12") (pin "2") (pinfunction "2_2") (pintype "passive"))
      (node (ref "U1") (pin "17") (pinfunction "PH5(OC4C)_17") (pintype "bidirectional"))
    )
    (net (code "104") (name "Net-(U1-PH6(OC2B))") (class "Default")
      (node (ref "R13") (pin "2") (pinfunction "2_2") (pintype "passive"))
      (node (ref "U1") (pin "18") (pinfunction "PH6(OC2B)_18") (pintype "bidirectional"))
    )
    (net (code "105") (name "Net-(U1-PJ0(RXD3{slash}PCINT9))") (class "Default")
      (node (ref "R59") (pin "2") (pinfunction "2_2") (pintype "passive"))
      (node (ref "U1") (pin "63") (pinfunction "PJ0(RXD3/PCINT9)_63") (pintype "bidirectional"))
    )
    (net (code "106") (name "Net-(U1-PJ1(TXD3{slash}PCINT10))") (class "Default")
      (node (ref "R58") (pin "2") (pinfunction "2_2") (pintype "passive"))
      (node (ref "U1") (pin "64") (pinfunction "PJ1(TXD3/PCINT10)_64") (pintype "bidirectional"))
    )
    (net (code "107") (name "Net-(U1-PK0(ADC8{slash}PCINT16))") (class "Default")
      (node (ref "R51") (pin "2") (pinfunction "2_2") (pintype "passive"))
      (node (ref "U1") (pin "89") (pinfunction "PK0(ADC8/PCINT16)_89") (pintype "bidirectional"))
    )
    (net (code "108") (name "Net-(U1-PK1(ADC9{slash}PCINT17))") (class "Default")
      (node (ref "R53") (pin "2") (pinfunction "2_2") (pintype "passive"))
      (node (ref "U1") (pin "88") (pinfunction "PK1(ADC9/PCINT17)_88") (pintype "bidirectional"))
    )
    (net (code "109") (name "Net-(U1-PK5(ADC13{slash}PCINT21))") (class "Default")
      (node (ref "R43") (pin "2") (pinfunction "2_2") (pintype "passive"))
      (node (ref "R44") (pin "2") (pinfunction "2_2") (pintype "passive"))
      (node (ref "U1") (pin "84") (pinfunction "PK5(ADC13/PCINT21)_84") (pintype "bidirectional"))
    )
    (net (code "110") (name "Net-(U1-PK6(ADC14{slash}PCINT22))") (class "Default")
      (node (ref "R56") (pin "1") (pinfunction "1_1") (pintype "passive"))
      (node (ref "R57") (pin "2") (pinfunction "2_2") (pintype "passive"))
      (node (ref "U1") (pin "83") (pinfunction "PK6(ADC14/PCINT22)_83") (pintype "bidirectional"))
    )
    (net (code "111") (name "Net-(U1-PK7(ADC15{slash}PCINT23))") (class "Default")
      (node (ref "DC21") (pin "1") (pinfunction "1_1") (pintype "passive"))
      (node (ref "R1") (pin "1") (pinfunction "1_1") (pintype "passive"))
      (node (ref "U1") (pin "82") (pinfunction "PK7(ADC15/PCINT23)_82") (pintype "bidirectional"))
    )
    (net (code "112") (name "Net-(U1-RESET)") (class "Default")
      (node (ref "BOOTLOAD") (pin "2") (pinfunction "2_2") (pintype "passive"))
      (node (ref "D2") (pin "A") (pinfunction "A_A") (pintype "passive"))
      (node (ref "DC11") (pin "1") (pinfunction "1_1") (pintype "passive"))
      (node (ref "JP1") (pin "4") (pinfunction "4_4") (pintype "passive"))
      (node (ref "R16") (pin "2") (pinfunction "2_2") (pintype "passive"))
      (node (ref "U1") (pin "30") (pinfunction "RESET_30") (pintype "input"))
    )
    (net (code "113") (name "Net-(U1-XTAL1)") (class "Default")
      (node (ref "C8") (pin "2") (pinfunction "2_2") (pintype "passive"))
      (node (ref "O1") (pin "1") (pinfunction "1_1") (pintype "passive"))
      (node (ref "U1") (pin "34") (pinfunction "XTAL1_34") (pintype "input"))
    )
    (net (code "114") (name "Net-(U1-XTAL2)") (class "Default")
      (node (ref "C7") (pin "2") (pinfunction "2_2") (pintype "passive"))
      (node (ref "O1") (pin "2") (pinfunction "2_2") (pintype "passive"))
      (node (ref "U1") (pin "33") (pinfunction "XTAL2_33") (pintype "output"))
    )
    (net (code "115") (name "Net-(U2-NETLIGHT)") (class "Default")
      (node (ref "R17") (pin "2") (pinfunction "2_2") (pintype "passive"))
      (node (ref "U2") (pin "13") (pinfunction "NETLIGHT_13") (pintype "output"))
    )
    (net (code "116") (name "Net-(U2-RF_ANT)") (class "Default")
      (node (ref "U2") (pin "39") (pinfunction "RF_ANT_39") (pintype "bidirectional"))
      (node (ref "X1") (pin "1") (pinfunction "1_1") (pintype "passive"))
    )
    (net (code "117") (name "Net-(U2-RI)") (class "Default")
      (node (ref "D2") (pin "K") (pinfunction "K_K") (pintype "passive"))
      (node (ref "U2") (pin "26") (pinfunction "RI_26") (pintype "output"))
    )
    (net (code "118") (name "Net-(U2-RXD)") (class "Default")
      (node (ref "R14") (pin "1") (pinfunction "1_1") (pintype "passive"))
      (node (ref "R29") (pin "2") (pinfunction "2_2") (pintype "passive"))
      (node (ref "U2") (pin "21") (pinfunction "RXD_21") (pintype "input"))
    )
    (net (code "119") (name "Net-(U2-SIM_CLK)") (class "Default")
      (node (ref "R11") (pin "1") (pinfunction "1_1") (pintype "passive"))
      (node (ref "U2") (pin "30") (pinfunction "SIM_CLK_30") (pintype "output"))
    )
    (net (code "120") (name "Net-(U2-SIM_DATA)") (class "Default")
      (node (ref "R47") (pin "1") (pinfunction "1_1") (pintype "passive"))
      (node (ref "U2") (pin "29") (pinfunction "SIM_DATA_29") (pintype "bidirectional"))
    )
    (net (code "121") (name "Net-(U2-SIM_GND)") (class "Default")
      (node (ref "U$2") (pin "SIM_GND") (pinfunction "SIM_GND_SIM_GND") (pintype "bidirectional"))
      (node (ref "U2") (pin "31") (pinfunction "SIM_GND_31") (pintype "power_in"))
    )
    (net (code "122") (name "Net-(U2-SIM_RST)") (class "Default")
      (node (ref "R10") (pin "1") (pinfunction "1_1") (pintype "passive"))
      (node (ref "U2") (pin "28") (pinfunction "SIM_RST_28") (pintype "output"))
    )
    (net (code "123") (name "Net-(U2-SIM_VDD)") (class "Default")
      (node (ref "DC15") (pin "2") (pinfunction "2_2") (pintype "passive"))
      (node (ref "U$2") (pin "SIM_VDD") (pinfunction "SIM_VDD_SIM_VDD") (pintype "bidirectional"))
      (node (ref "U2") (pin "27") (pinfunction "SIM_VDD_27") (pintype "power_in"))
    )
    (net (code "124") (name "Net-(U2-TXD)") (class "Default")
      (node (ref "R15") (pin "1") (pinfunction "1_1") (pintype "passive"))
      (node (ref "U2") (pin "22") (pinfunction "TXD_22") (pintype "output"))
    )
    (net (code "125") (name "VDD") (class "Default")
      (node (ref "DC1") (pin "1") (pinfunction "1_1") (pintype "passive"))
      (node (ref "DC18") (pin "2") (pinfunction "2_2") (pintype "passive"))
      (node (ref "DC2") (pin "1") (pinfunction "1_1") (pintype "passive"))
      (node (ref "DC3") (pin "1") (pinfunction "1_1") (pintype "passive"))
      (node (ref "DC4") (pin "1") (pinfunction "1_1") (pintype "passive"))
      (node (ref "DC5") (pin "1") (pinfunction "1_1") (pintype "passive"))
      (node (ref "L1") (pin "2") (pinfunction "2_2") (pintype "passive"))
      (node (ref "U1") (pin "10") (pinfunction "VCC_10") (pintype "power_in"))
      (node (ref "U1") (pin "100") (pinfunction "AVCC_100") (pintype "power_in"))
      (node (ref "U1") (pin "31") (pinfunction "VCC1_31") (pintype "power_in"))
      (node (ref "U1") (pin "61") (pinfunction "VCC2_61") (pintype "power_in"))
      (node (ref "U1") (pin "80") (pinfunction "VCC3_80") (pintype "power_in"))
    )
    (net (code "126") (name "unconnected-(IC3-I+_1-Pad2)") (class "Default")
      (node (ref "IC3") (pin "2") (pinfunction "I+_1_2") (pintype "bidirectional"))
    )
    (net (code "127") (name "unconnected-(IC3-I-_0-Pad3)") (class "Default")
      (node (ref "IC3") (pin "3") (pinfunction "I-_0_3") (pintype "bidirectional"))
    )
    (net (code "128") (name "unconnected-(JP12-Pad2)") (class "Default")
      (node (ref "JP12") (pin "2") (pinfunction "2_2") (pintype "passive"))
    )
    (net (code "129") (name "unconnected-(JP15-Pad2)") (class "Default")
      (node (ref "JP15") (pin "2") (pinfunction "2_2") (pintype "passive"))
    )
    (net (code "130") (name "unconnected-(U$1-PadCD)") (class "Default")
      (node (ref "U$1") (pin "CD") (pinfunction "CD_CD") (pintype "output"))
    )
    (net (code "131") (name "unconnected-(U1-(A8)PC0-Pad53)") (class "Default")
      (node (ref "U1") (pin "53") (pinfunction "(A8)PC0_53") (pintype "bidirectional"))
    )
    (net (code "132") (name "unconnected-(U1-(A9)PC1-Pad54)") (class "Default")
      (node (ref "U1") (pin "54") (pinfunction "(A9)PC1_54") (pintype "bidirectional"))
    )
    (net (code "133") (name "unconnected-(U1-(A10)PC2-Pad55)") (class "Default")
      (node (ref "U1") (pin "55") (pinfunction "(A10)PC2_55") (pintype "bidirectional"))
    )
    (net (code "134") (name "unconnected-(U1-(A11)PC3-Pad56)") (class "Default")
      (node (ref "U1") (pin "56") (pinfunction "(A11)PC3_56") (pintype "bidirectional"))
    )
    (net (code "135") (name "unconnected-(U1-(A12)PC4-Pad57)") (class "Default")
      (node (ref "U1") (pin "57") (pinfunction "(A12)PC4_57") (pintype "bidirectional"))
    )
    (net (code "136") (name "unconnected-(U1-(A13)PC5-Pad58)") (class "Default")
      (node (ref "U1") (pin "58") (pinfunction "(A13)PC5_58") (pintype "bidirectional"))
    )
    (net (code "137") (name "unconnected-(U1-(A14)PC6-Pad59)") (class "Default")
      (node (ref "U1") (pin "59") (pinfunction "(A14)PC6_59") (pintype "bidirectional"))
    )
    (net (code "138") (name "unconnected-(U1-(A15)PC7-Pad60)") (class "Default")
      (node (ref "U1") (pin "60") (pinfunction "(A15)PC7_60") (pintype "bidirectional"))
    )
    (net (code "139") (name "unconnected-(U1-(AD0)PA0-Pad78)") (class "Default")
      (node (ref "U1") (pin "78") (pinfunction "(AD0)PA0_78") (pintype "bidirectional"))
    )
    (net (code "140") (name "unconnected-(U1-(AD1)PA1-Pad77)") (class "Default")
      (node (ref "U1") (pin "77") (pinfunction "(AD1)PA1_77") (pintype "bidirectional"))
    )
    (net (code "141") (name "unconnected-(U1-(AD2)PA2-Pad76)") (class "Default")
      (node (ref "U1") (pin "76") (pinfunction "(AD2)PA2_76") (pintype "bidirectional"))
    )
    (net (code "142") (name "unconnected-(U1-(AD5)PA5-Pad73)") (class "Default")
      (node (ref "U1") (pin "73") (pinfunction "(AD5)PA5_73") (pintype "bidirectional"))
    )
    (net (code "143") (name "unconnected-(U1-(AD6)PA6-Pad72)") (class "Default")
      (node (ref "U1") (pin "72") (pinfunction "(AD6)PA6_72") (pintype "bidirectional"))
    )
    (net (code "144") (name "unconnected-(U1-(AD7)PA7-Pad71)") (class "Default")
      (node (ref "U1") (pin "71") (pinfunction "(AD7)PA7_71") (pintype "bidirectional"))
    )
    (net (code "145") (name "unconnected-(U1-(ALE)PG2-Pad70)") (class "Default")
      (node (ref "U1") (pin "70") (pinfunction "(ALE)PG2_70") (pintype "bidirectional"))
    )
    (net (code "146") (name "unconnected-(U1-(CLKO{slash}ICP3{slash}INT7)PE7-Pad9)") (class "Default")
      (node (ref "U1") (pin "9") (pinfunction "(CLKO/ICP3/INT7)PE7_9") (pintype "bidirectional"))
    )
    (net (code "147") (name "unconnected-(U1-(ICP1)PD4-Pad47)") (class "Default")
      (node (ref "U1") (pin "47") (pinfunction "(ICP1)PD4_47") (pintype "bidirectional"))
    )
    (net (code "148") (name "unconnected-(U1-(OC0A{slash}OC1C{slash}PCINT7)PB7-Pad26)") (class "Default")
      (node (ref "U1") (pin "26") (pinfunction "(OC0A/OC1C/PCINT7)PB7_26") (pintype "bidirectional"))
    )
    (net (code "149") (name "unconnected-(U1-(T0)PD7-Pad50)") (class "Default")
      (node (ref "U1") (pin "50") (pinfunction "(T0)PD7_50") (pintype "bidirectional"))
    )
    (net (code "150") (name "unconnected-(U1-(T1)PD6-Pad49)") (class "Default")
      (node (ref "U1") (pin "49") (pinfunction "(T1)PD6_49") (pintype "bidirectional"))
    )
    (net (code "151") (name "unconnected-(U1-(T3{slash}INT6)PE6-Pad8)") (class "Default")
      (node (ref "U1") (pin "8") (pinfunction "(T3/INT6)PE6_8") (pintype "bidirectional"))
    )
    (net (code "152") (name "unconnected-(U1-(TOSC1)PG4-Pad29)") (class "Default")
      (node (ref "U1") (pin "29") (pinfunction "(TOSC1)PG4_29") (pintype "bidirectional"))
    )
    (net (code "153") (name "unconnected-(U1-(TOSC2)PG3-Pad28)") (class "Default")
      (node (ref "U1") (pin "28") (pinfunction "(TOSC2)PG3_28") (pintype "bidirectional"))
    )
    (net (code "154") (name "unconnected-(U1-(XCK0{slash}AIN0)PE2-Pad4)") (class "Default")
      (node (ref "U1") (pin "4") (pinfunction "(XCK0/AIN0)PE2_4") (pintype "bidirectional"))
    )
    (net (code "155") (name "unconnected-(U1-(XCK1)PD5-Pad48)") (class "Default")
      (node (ref "U1") (pin "48") (pinfunction "(XCK1)PD5_48") (pintype "bidirectional"))
    )
    (net (code "156") (name "unconnected-(U1-AREF-Pad98)") (class "Default")
      (node (ref "U1") (pin "98") (pinfunction "AREF_98") (pintype "bidirectional"))
    )
    (net (code "157") (name "unconnected-(U1-PH2(XCK2)-Pad14)") (class "Default")
      (node (ref "U1") (pin "14") (pinfunction "PH2(XCK2)_14") (pintype "bidirectional"))
    )
    (net (code "158") (name "unconnected-(U1-PH7(T4)-Pad27)") (class "Default")
      (node (ref "U1") (pin "27") (pinfunction "PH7(T4)_27") (pintype "bidirectional"))
    )
    (net (code "159") (name "unconnected-(U1-PJ2(XCK3{slash}PCINT11)-Pad65)") (class "Default")
      (node (ref "U1") (pin "65") (pinfunction "PJ2(XCK3/PCINT11)_65") (pintype "bidirectional"))
    )
    (net (code "160") (name "unconnected-(U1-PJ3(PCINT12)-Pad66)") (class "Default")
      (node (ref "U1") (pin "66") (pinfunction "PJ3(PCINT12)_66") (pintype "bidirectional"))
    )
    (net (code "161") (name "unconnected-(U1-PJ4(PCINT13)-Pad67)") (class "Default")
      (node (ref "U1") (pin "67") (pinfunction "PJ4(PCINT13)_67") (pintype "bidirectional"))
    )
    (net (code "162") (name "unconnected-(U1-PJ5(PCINT14)-Pad68)") (class "Default")
      (node (ref "U1") (pin "68") (pinfunction "PJ5(PCINT14)_68") (pintype "bidirectional"))
    )
    (net (code "163") (name "unconnected-(U1-PJ6(PCINT15)-Pad69)") (class "Default")
      (node (ref "U1") (pin "69") (pinfunction "PJ6(PCINT15)_69") (pintype "bidirectional"))
    )
    (net (code "164") (name "unconnected-(U1-PJ7-Pad79)") (class "Default")
      (node (ref "U1") (pin "79") (pinfunction "PJ7_79") (pintype "bidirectional"))
    )
    (net (code "165") (name "unconnected-(U1-PK2(ADC10{slash}PCINT18)-Pad87)") (class "Default")
      (node (ref "U1") (pin "87") (pinfunction "PK2(ADC10/PCINT18)_87") (pintype "bidirectional"))
    )
    (net (code "166") (name "unconnected-(U1-PK3(ADC11{slash}PCINT19)-Pad86)") (class "Default")
      (node (ref "U1") (pin "86") (pinfunction "PK3(ADC11/PCINT19)_86") (pintype "bidirectional"))
    )
    (net (code "167") (name "unconnected-(U1-PK4(ADC12{slash}PCINT20)-Pad85)") (class "Default")
      (node (ref "U1") (pin "85") (pinfunction "PK4(ADC12/PCINT20)_85") (pintype "bidirectional"))
    )
    (net (code "168") (name "unconnected-(U1-PL0(ICP4)-Pad35)") (class "Default")
      (node (ref "U1") (pin "35") (pinfunction "PL0(ICP4)_35") (pintype "bidirectional"))
    )
    (net (code "169") (name "unconnected-(U1-PL1(ICP5)-Pad36)") (class "Default")
      (node (ref "U1") (pin "36") (pinfunction "PL1(ICP5)_36") (pintype "bidirectional"))
    )
    (net (code "170") (name "unconnected-(U1-PL2(T5)-Pad37)") (class "Default")
      (node (ref "U1") (pin "37") (pinfunction "PL2(T5)_37") (pintype "bidirectional"))
    )
    (net (code "171") (name "unconnected-(U1-PL3(OC5A)-Pad38)") (class "Default")
      (node (ref "U1") (pin "38") (pinfunction "PL3(OC5A)_38") (pintype "bidirectional"))
    )
    (net (code "172") (name "unconnected-(U1-PL4(OC5B)-Pad39)") (class "Default")
      (node (ref "U1") (pin "39") (pinfunction "PL4(OC5B)_39") (pintype "bidirectional"))
    )
    (net (code "173") (name "unconnected-(U1-PL5(OC5C)-Pad40)") (class "Default")
      (node (ref "U1") (pin "40") (pinfunction "PL5(OC5C)_40") (pintype "bidirectional"))
    )
    (net (code "174") (name "unconnected-(U1-PL6-Pad41)") (class "Default")
      (node (ref "U1") (pin "41") (pinfunction "PL6_41") (pintype "bidirectional"))
    )
    (net (code "175") (name "unconnected-(U1-PL7-Pad42)") (class "Default")
      (node (ref "U1") (pin "42") (pinfunction "PL7_42") (pintype "bidirectional"))
    )
    (net (code "176") (name "unconnected-(U2-CTS-Pad23)") (class "Default")
      (node (ref "U2") (pin "23") (pinfunction "CTS_23") (pintype "output"))
    )
    (net (code "177") (name "unconnected-(U2-DBG_RXD-Pad14)") (class "Default")
      (node (ref "U2") (pin "14") (pinfunction "DBG_RXD_14") (pintype "input"))
    )
    (net (code "178") (name "unconnected-(U2-DBG_TXD-Pad15)") (class "Default")
      (node (ref "U2") (pin "15") (pinfunction "DBG_TXD_15") (pintype "output"))
    )
    (net (code "179") (name "unconnected-(U2-DCD-Pad25)") (class "Default")
      (node (ref "U2") (pin "25") (pinfunction "DCD_25") (pintype "output"))
    )
    (net (code "180") (name "unconnected-(U2-DTR-Pad20)") (class "Default")
      (node (ref "U2") (pin "20") (pinfunction "DTR_20") (pintype "input"))
    )
    (net (code "181") (name "unconnected-(U2-EMERG_OFF-Pad11)") (class "Default")
      (node (ref "U2") (pin "11") (pinfunction "EMERG_OFF_11") (pintype "input"))
    )
    (net (code "182") (name "unconnected-(U2-LOUDSPKN-Pad8)") (class "Default")
      (node (ref "U2") (pin "8") (pinfunction "LOUDSPKN_8") (pintype "output"))
    )
    (net (code "183") (name "unconnected-(U2-LOUDSPKP-Pad9)") (class "Default")
      (node (ref "U2") (pin "9") (pinfunction "LOUDSPKP_9") (pintype "output"))
    )
    (net (code "184") (name "unconnected-(U2-MIC1N-Pad5)") (class "Default")
      (node (ref "U2") (pin "5") (pinfunction "MIC1N_5") (pintype "input"))
    )
    (net (code "185") (name "unconnected-(U2-MIC1P-Pad4)") (class "Default")
      (node (ref "U2") (pin "4") (pinfunction "MIC1P_4") (pintype "input"))
    )
    (net (code "186") (name "unconnected-(U2-MIC2N-Pad3)") (class "Default")
      (node (ref "U2") (pin "3") (pinfunction "MIC2N_3") (pintype "input"))
    )
    (net (code "187") (name "unconnected-(U2-MIC2P-Pad2)") (class "Default")
      (node (ref "U2") (pin "2") (pinfunction "MIC2P_2") (pintype "input"))
    )
    (net (code "188") (name "unconnected-(U2-RTS-Pad24)") (class "Default")
      (node (ref "U2") (pin "24") (pinfunction "RTS_24") (pintype "input"))
    )
    (net (code "189") (name "unconnected-(U2-SPK1N-Pad6)") (class "Default")
      (node (ref "U2") (pin "6") (pinfunction "SPK1N_6") (pintype "output"))
    )
    (net (code "190") (name "unconnected-(U2-SPK1P-Pad7)") (class "Default")
      (node (ref "U2") (pin "7") (pinfunction "SPK1P_7") (pintype "output"))
    )
    (net (code "191") (name "unconnected-(U2-STATUS-Pad12)") (class "Default")
      (node (ref "U2") (pin "12") (pinfunction "STATUS_12") (pintype "output"))
    )
  )
)
